# Arduino_lab_v1_2.net
KiCad netlist of a schematic drawn in EAGLE
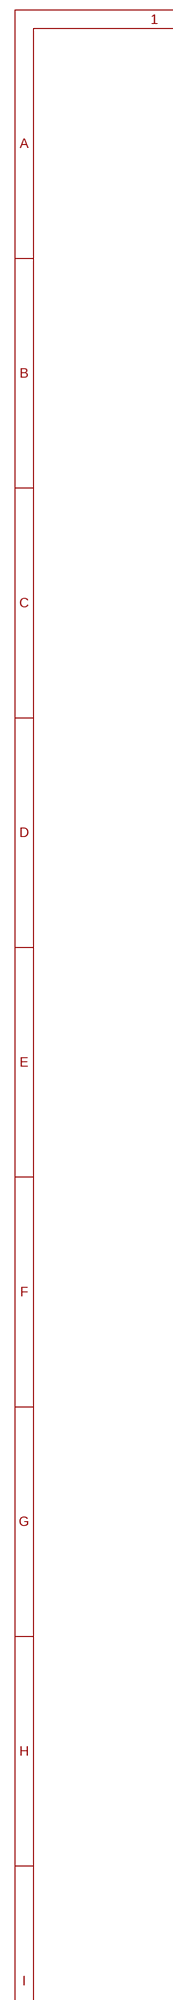
[diagram p0: schematic, sheet 1, part 1 of 2]
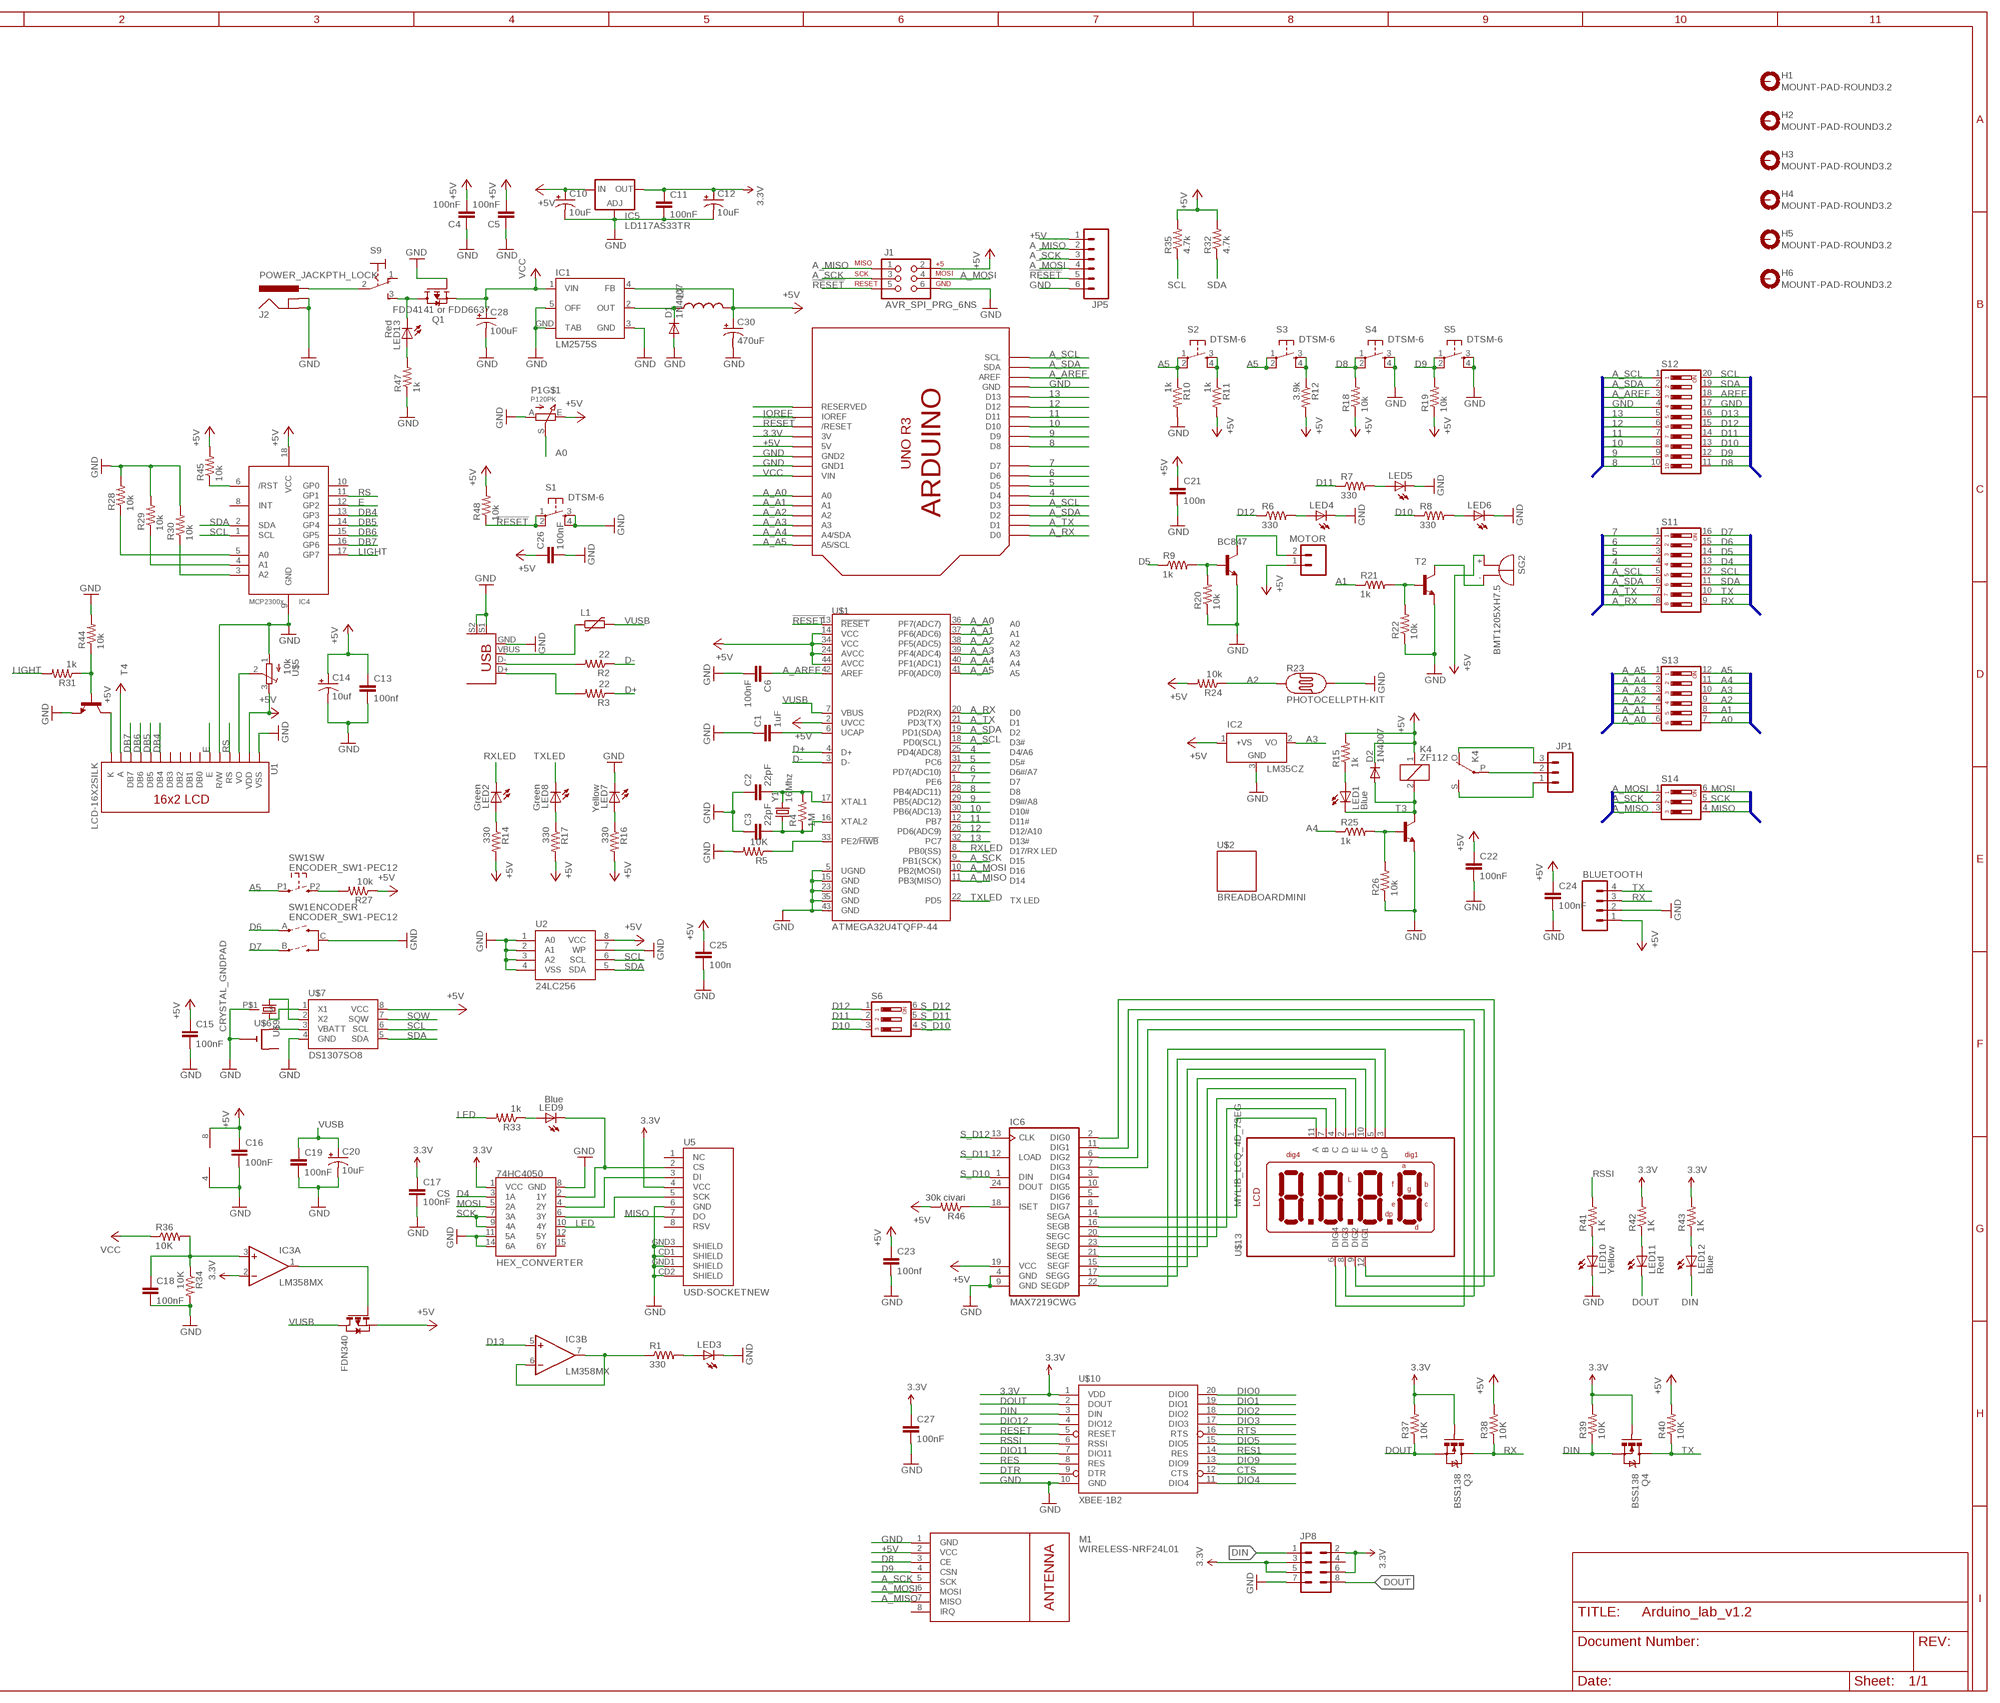
[diagram p1: schematic, sheet 1, part 2 of 2]

(export (version "E")
  (design (tool "Eeschema 10.0.6"))
  (components
    (comp (ref "74HC4050")
      (value "HEX_CONVERTER")
      (footprint "eagle-import:SO016")
      (libsource (lib "eagle-import") (part "HEX_CONVERTER"))
    )
    (comp (ref "BC847")
      (value "MMBT2222ALT1-NPN-SOT23-BEC")
      (footprint "eagle-import:SOT23-BEC")
      (libsource (lib "eagle-import") (part "-NPN-SOT23-BECMMBT2222ALT1"))
    )
    (comp (ref "BLUETOOTH")
      (value "M04PTH")
      (footprint "eagle-import:1X04")
      (libsource (lib "eagle-import") (part "M04PTH"))
    )
    (comp (ref "C1")
      (value "1uF")
      (footprint "eagle-import:1206")
      (libsource (lib "eagle-import") (part "CAP1206"))
    )
    (comp (ref "C2")
      (value "22pF")
      (footprint "eagle-import:0805")
      (libsource (lib "eagle-import") (part "CAP0805"))
    )
    (comp (ref "C3")
      (value "22pF")
      (footprint "eagle-import:0805")
      (libsource (lib "eagle-import") (part "CAP0805"))
    )
    (comp (ref "C4")
      (value "100nF")
      (footprint "eagle-import:0805")
      (libsource (lib "eagle-import") (part "CAP0805"))
    )
    (comp (ref "C5")
      (value "100nF")
      (footprint "eagle-import:0805")
      (libsource (lib "eagle-import") (part "CAP0805"))
    )
    (comp (ref "C6")
      (value "100nF")
      (footprint "eagle-import:0805")
      (libsource (lib "eagle-import") (part "CAP0805"))
    )
    (comp (ref "C10")
      (value "10uF")
      (footprint "eagle-import:EIA3216")
      (libsource (lib "eagle-import") (part "CAP_POL1206"))
    )
    (comp (ref "C11")
      (value "100nF")
      (footprint "eagle-import:0805")
      (libsource (lib "eagle-import") (part "CAP0805"))
    )
    (comp (ref "C12")
      (value "10uF")
      (footprint "eagle-import:EIA3216")
      (libsource (lib "eagle-import") (part "CAP_POL1206"))
    )
    (comp (ref "C13")
      (value "100nf")
      (footprint "eagle-import:0805")
      (libsource (lib "eagle-import") (part "CAP0805"))
    )
    (comp (ref "C14")
      (value "10uf")
      (footprint "eagle-import:EIA3216")
      (libsource (lib "eagle-import") (part "CAP_POL1206"))
    )
    (comp (ref "C15")
      (value "100nF")
      (footprint "eagle-import:0805")
      (libsource (lib "eagle-import") (part "CAP0805"))
    )
    (comp (ref "C16")
      (value "100nF")
      (footprint "eagle-import:0805")
      (libsource (lib "eagle-import") (part "CAP0805"))
    )
    (comp (ref "C17")
      (value "100nF")
      (footprint "eagle-import:0805")
      (libsource (lib "eagle-import") (part "CAP0805"))
    )
    (comp (ref "C18")
      (value "100nF")
      (footprint "eagle-import:0805")
      (libsource (lib "eagle-import") (part "CAP0805"))
    )
    (comp (ref "C19")
      (value "100nF")
      (footprint "eagle-import:0805")
      (libsource (lib "eagle-import") (part "CAP0805"))
    )
    (comp (ref "C20")
      (value "10uF")
      (footprint "eagle-import:EIA3216")
      (libsource (lib "eagle-import") (part "CAP_POL1206"))
    )
    (comp (ref "C21")
      (value "100n")
      (footprint "eagle-import:0805")
      (libsource (lib "eagle-import") (part "CAP0805"))
    )
    (comp (ref "C22")
      (value "100nF")
      (footprint "eagle-import:0805")
      (libsource (lib "eagle-import") (part "CAP0805"))
    )
    (comp (ref "C23")
      (value "100nf")
      (footprint "eagle-import:0805")
      (libsource (lib "eagle-import") (part "CAP0805"))
    )
    (comp (ref "C24")
      (value "100nF")
      (footprint "eagle-import:0805")
      (libsource (lib "eagle-import") (part "CAP0805"))
    )
    (comp (ref "C25")
      (value "100n")
      (footprint "eagle-import:0805")
      (libsource (lib "eagle-import") (part "CAP0805"))
    )
    (comp (ref "C26")
      (value "100nF")
      (footprint "eagle-import:0805")
      (libsource (lib "eagle-import") (part "CAP0805"))
    )
    (comp (ref "C27")
      (value "100nF")
      (footprint "eagle-import:0805")
      (libsource (lib "eagle-import") (part "CAP0805"))
    )
    (comp (ref "C28")
      (value "100uF")
      (footprint "eagle-import:NIPPON_F80")
      (libsource (lib "eagle-import") (part "CAP_POLF80"))
    )
    (comp (ref "C30")
      (value "470uF")
      (footprint "eagle-import:PANASONIC_G")
      (libsource (lib "eagle-import") (part "CAP_POLG"))
    )
    (comp (ref "D1")
      (value "1N4007")
      (footprint "eagle-import:SMA-DIODE_ALT")
      (libsource (lib "eagle-import") (part "DIODESMA-ALT"))
    )
    (comp (ref "D2")
      (value "1N4007")
      (footprint "eagle-import:SMA-DIODE_ALT")
      (libsource (lib "eagle-import") (part "DIODESMA-ALT"))
    )
    (comp (ref "FDN340")
      (value "PMOSSOT23")
      (footprint "eagle-import:SOT-23")
      (libsource (lib "eagle-import") (part "PMOSSOT23"))
    )
    (comp (ref "H1")
      (value "MOUNT-PAD-ROUND3.2")
      (footprint "eagle-import:3,2-PAD")
      (libsource (lib "eagle-import") (part "MOUNT-PAD-ROUND3.2"))
    )
    (comp (ref "H2")
      (value "MOUNT-PAD-ROUND3.2")
      (footprint "eagle-import:3,2-PAD")
      (libsource (lib "eagle-import") (part "MOUNT-PAD-ROUND3.2"))
    )
    (comp (ref "H3")
      (value "MOUNT-PAD-ROUND3.2")
      (footprint "eagle-import:3,2-PAD")
      (libsource (lib "eagle-import") (part "MOUNT-PAD-ROUND3.2"))
    )
    (comp (ref "H4")
      (value "MOUNT-PAD-ROUND3.2")
      (footprint "eagle-import:3,2-PAD")
      (libsource (lib "eagle-import") (part "MOUNT-PAD-ROUND3.2"))
    )
    (comp (ref "H5")
      (value "MOUNT-PAD-ROUND3.2")
      (footprint "eagle-import:3,2-PAD")
      (libsource (lib "eagle-import") (part "MOUNT-PAD-ROUND3.2"))
    )
    (comp (ref "H6")
      (value "MOUNT-PAD-ROUND3.2")
      (footprint "eagle-import:3,2-PAD")
      (libsource (lib "eagle-import") (part "MOUNT-PAD-ROUND3.2"))
    )
    (comp (ref "IC1")
      (value "LM2575S")
      (footprint "eagle-import:TO263-5")
      (libsource (lib "eagle-import") (part "LM2575S"))
    )
    (comp (ref "IC2")
      (value "LM35CZ")
      (footprint "eagle-import:TO92")
      (libsource (lib "eagle-import") (part "LM35CZ"))
    )
    (comp (ref "IC3")
      (value "LM358MX")
      (footprint "eagle-import:SO08")
      (libsource (lib "eagle-import") (part "LM358MX"))
    )
    (comp (ref "IC4")
      (value "MCP2300X/SO")
      (footprint "eagle-import:SO18W")
      (libsource (lib "eagle-import") (part "MCP2300X/SO"))
    )
    (comp (ref "IC5")
      (value "LD117AS33TR")
      (footprint "eagle-import:SOT223")
      (libsource (lib "eagle-import") (part "LD117A?S33TR"))
    )
    (comp (ref "IC6")
      (value "MAX7219CWG")
      (footprint "eagle-import:SO24W")
      (libsource (lib "eagle-import") (part "MAX7219WGC"))
    )
    (comp (ref "J1")
      (value "AVR_SPI_PRG_6NS")
      (footprint "eagle-import:2X3-NS")
      (libsource (lib "eagle-import") (part "AVR_SPI_PRG_6NS"))
    )
    (comp (ref "J2")
      (value "POWER_JACKPTH_LOCK")
      (footprint "eagle-import:POWER_JACK_PTH_LOCK")
      (libsource (lib "eagle-import") (part "POWER_JACKPTH_LOCK"))
    )
    (comp (ref "JP1")
      (value "M03-SCREW-5MM")
      (footprint "eagle-import:SCREWTERMINAL-5MM-3")
      (libsource (lib "eagle-import") (part "M03-SCREW-5MM"))
    )
    (comp (ref "JP5")
      (value "M06SIP")
      (footprint "eagle-import:1X06")
      (libsource (lib "eagle-import") (part "M06SIP"))
    )
    (comp (ref "JP8")
      (value "M04X2")
      (footprint "eagle-import:2X4")
      (libsource (lib "eagle-import") (part "M04X2"))
    )
    (comp (ref "K4")
      (value "ZF112")
      (footprint "eagle-import:ZF112")
      (libsource (lib "eagle-import") (part "ZF112"))
    )
    (comp (ref "L1")
      (value "FUSE_PTC-0805")
      (footprint "eagle-import:PTC0805")
      (libsource (lib "eagle-import") (part "FUSE_PTC-0805"))
    )
    (comp (ref "L2")
      (value "INDUCTORPWR")
      (footprint "eagle-import:CDRH125")
      (libsource (lib "eagle-import") (part "INDUCTORPWR"))
    )
    (comp (ref "LED1")
      (value "Blue")
      (footprint "eagle-import:CHIPLED_0805")
      (libsource (lib "eagle-import") (part "LEDCHIPLED_0805"))
    )
    (comp (ref "LED2")
      (value "Green")
      (footprint "eagle-import:CHIPLED_0805")
      (libsource (lib "eagle-import") (part "LEDCHIPLED_0805"))
    )
    (comp (ref "LED3")
      (value "LED5MM")
      (footprint "eagle-import:LED5MM")
      (libsource (lib "eagle-import") (part "LED5MM"))
    )
    (comp (ref "LED4")
      (value "LED5MM")
      (footprint "eagle-import:LED5MM")
      (libsource (lib "eagle-import") (part "LED5MM"))
    )
    (comp (ref "LED5")
      (value "LED5MM")
      (footprint "eagle-import:LED5MM")
      (libsource (lib "eagle-import") (part "LED5MM"))
    )
    (comp (ref "LED6")
      (value "LED5MM")
      (footprint "eagle-import:LED5MM")
      (libsource (lib "eagle-import") (part "LED5MM"))
    )
    (comp (ref "LED7")
      (value "Yellow")
      (footprint "eagle-import:CHIPLED_0805")
      (libsource (lib "eagle-import") (part "LEDCHIPLED_0805"))
    )
    (comp (ref "LED8")
      (value "Green")
      (footprint "eagle-import:CHIPLED_0805")
      (libsource (lib "eagle-import") (part "LEDCHIPLED_0805"))
    )
    (comp (ref "LED9")
      (value "Blue")
      (footprint "eagle-import:CHIPLED_0805")
      (libsource (lib "eagle-import") (part "LEDCHIPLED_0805"))
    )
    (comp (ref "LED10")
      (value "Yellow")
      (footprint "eagle-import:CHIPLED_0805")
      (libsource (lib "eagle-import") (part "LEDCHIPLED_0805"))
    )
    (comp (ref "LED11")
      (value "Red")
      (footprint "eagle-import:CHIPLED_0805")
      (libsource (lib "eagle-import") (part "LEDCHIPLED_0805"))
    )
    (comp (ref "LED12")
      (value "Blue")
      (footprint "eagle-import:CHIPLED_0805")
      (libsource (lib "eagle-import") (part "LEDCHIPLED_0805"))
    )
    (comp (ref "LED13")
      (value "Red")
      (footprint "eagle-import:CHIPLED_0805")
      (libsource (lib "eagle-import") (part "LEDCHIPLED_0805"))
    )
    (comp (ref "M1")
      (value "WIRELESS-NRF24L01")
      (footprint "eagle-import:WIRELESS-NRF24L01")
      (libsource (lib "eagle-import") (part "WIRELESS-NRF24L01"))
    )
    (comp (ref "MOTOR")
      (value "M023.5MM")
      (footprint "eagle-import:SCREWTERMINAL-3.5MM-2")
      (libsource (lib "eagle-import") (part "M023.5MM"))
    )
    (comp (ref "P1")
      (value "P120PK")
      (footprint "eagle-import:P120PK")
      (libsource (lib "eagle-import") (part "P120PK"))
    )
    (comp (ref "Q1")
      (value "FDD4141 or FDD6637")
      (footprint "eagle-import:TO252")
      (libsource (lib "eagle-import") (part "FDD4141TO252"))
    )
    (comp (ref "Q3")
      (value "BSS138")
      (footprint "eagle-import:SOT23-3")
      (libsource (lib "eagle-import") (part "MOSFET-NCHANNELSMD"))
    )
    (comp (ref "Q4")
      (value "BSS138")
      (footprint "eagle-import:SOT23-3")
      (libsource (lib "eagle-import") (part "MOSFET-NCHANNELSMD"))
    )
    (comp (ref "R1")
      (value "330")
      (footprint "eagle-import:0805")
      (libsource (lib "eagle-import") (part "RESISTOR0805-RES"))
    )
    (comp (ref "R2")
      (value "22")
      (footprint "eagle-import:0805")
      (libsource (lib "eagle-import") (part "RESISTOR0805-RES"))
    )
    (comp (ref "R3")
      (value "22")
      (footprint "eagle-import:0805")
      (libsource (lib "eagle-import") (part "RESISTOR0805-RES"))
    )
    (comp (ref "R4")
      (value "1M")
      (footprint "eagle-import:0805")
      (libsource (lib "eagle-import") (part "RESISTOR0805-RES"))
    )
    (comp (ref "R5")
      (value "10K")
      (footprint "eagle-import:0805")
      (libsource (lib "eagle-import") (part "RESISTOR0805-RES"))
    )
    (comp (ref "R6")
      (value "330")
      (footprint "eagle-import:0805")
      (libsource (lib "eagle-import") (part "RESISTOR0805-RES"))
    )
    (comp (ref "R7")
      (value "330")
      (footprint "eagle-import:0805")
      (libsource (lib "eagle-import") (part "RESISTOR0805-RES"))
    )
    (comp (ref "R8")
      (value "330")
      (footprint "eagle-import:0805")
      (libsource (lib "eagle-import") (part "RESISTOR0805-RES"))
    )
    (comp (ref "R9")
      (value "1k")
      (footprint "eagle-import:0805")
      (libsource (lib "eagle-import") (part "RESISTOR0805-RES"))
    )
    (comp (ref "R10")
      (value "1k")
      (footprint "eagle-import:0805")
      (libsource (lib "eagle-import") (part "RESISTOR0805-RES"))
    )
    (comp (ref "R11")
      (value "1k")
      (footprint "eagle-import:0805")
      (libsource (lib "eagle-import") (part "RESISTOR0805-RES"))
    )
    (comp (ref "R12")
      (value "3.9k")
      (footprint "eagle-import:0805")
      (libsource (lib "eagle-import") (part "RESISTOR0805-RES"))
    )
    (comp (ref "R14")
      (value "330")
      (footprint "eagle-import:0805")
      (libsource (lib "eagle-import") (part "RESISTOR0805-RES"))
    )
    (comp (ref "R15")
      (value "1k")
      (footprint "eagle-import:0805")
      (libsource (lib "eagle-import") (part "RESISTOR0805-RES"))
    )
    (comp (ref "R16")
      (value "330")
      (footprint "eagle-import:0805")
      (libsource (lib "eagle-import") (part "RESISTOR0805-RES"))
    )
    (comp (ref "R17")
      (value "330")
      (footprint "eagle-import:0805")
      (libsource (lib "eagle-import") (part "RESISTOR0805-RES"))
    )
    (comp (ref "R18")
      (value "10k")
      (footprint "eagle-import:0805")
      (libsource (lib "eagle-import") (part "RESISTOR0805-RES"))
    )
    (comp (ref "R19")
      (value "10k")
      (footprint "eagle-import:0805")
      (libsource (lib "eagle-import") (part "RESISTOR0805-RES"))
    )
    (comp (ref "R20")
      (value "10k")
      (footprint "eagle-import:0805")
      (libsource (lib "eagle-import") (part "RESISTOR0805-RES"))
    )
    (comp (ref "R21")
      (value "1k")
      (footprint "eagle-import:0805")
      (libsource (lib "eagle-import") (part "RESISTOR0805-RES"))
    )
    (comp (ref "R22")
      (value "10k")
      (footprint "eagle-import:0805")
      (libsource (lib "eagle-import") (part "RESISTOR0805-RES"))
    )
    (comp (ref "R23")
      (value "PHOTOCELLPTH-KIT")
      (footprint "eagle-import:PHOTOCELL-KIT")
      (libsource (lib "eagle-import") (part "PHOTOCELLPTH-KIT"))
    )
    (comp (ref "R24")
      (value "10k")
      (footprint "eagle-import:0805")
      (libsource (lib "eagle-import") (part "RESISTOR0805-RES"))
    )
    (comp (ref "R25")
      (value "1k")
      (footprint "eagle-import:0805")
      (libsource (lib "eagle-import") (part "RESISTOR0805-RES"))
    )
    (comp (ref "R26")
      (value "10k")
      (footprint "eagle-import:0805")
      (libsource (lib "eagle-import") (part "RESISTOR0805-RES"))
    )
    (comp (ref "R27")
      (value "10k")
      (footprint "eagle-import:0805")
      (libsource (lib "eagle-import") (part "RESISTOR0805-RES"))
    )
    (comp (ref "R28")
      (value "10k")
      (footprint "eagle-import:0805")
      (libsource (lib "eagle-import") (part "RESISTOR0805-RES"))
    )
    (comp (ref "R29")
      (value "10k")
      (footprint "eagle-import:0805")
      (libsource (lib "eagle-import") (part "RESISTOR0805-RES"))
    )
    (comp (ref "R30")
      (value "10k")
      (footprint "eagle-import:0805")
      (libsource (lib "eagle-import") (part "RESISTOR0805-RES"))
    )
    (comp (ref "R31")
      (value "1k")
      (footprint "eagle-import:0805")
      (libsource (lib "eagle-import") (part "RESISTOR0805-RES"))
    )
    (comp (ref "R32")
      (value "4.7k")
      (footprint "eagle-import:0805")
      (libsource (lib "eagle-import") (part "RESISTOR0805-RES"))
    )
    (comp (ref "R33")
      (value "1k")
      (footprint "eagle-import:0805")
      (libsource (lib "eagle-import") (part "RESISTOR0805-RES"))
    )
    (comp (ref "R34")
      (value "10K")
      (footprint "eagle-import:0805")
      (libsource (lib "eagle-import") (part "RESISTOR0805-RES"))
    )
    (comp (ref "R35")
      (value "4.7k")
      (footprint "eagle-import:0805")
      (libsource (lib "eagle-import") (part "RESISTOR0805-RES"))
    )
    (comp (ref "R36")
      (value "10K")
      (footprint "eagle-import:0805")
      (libsource (lib "eagle-import") (part "RESISTOR0805-RES"))
    )
    (comp (ref "R37")
      (value "10K")
      (footprint "eagle-import:0805")
      (libsource (lib "eagle-import") (part "RESISTOR0805-RES"))
    )
    (comp (ref "R38")
      (value "10K")
      (footprint "eagle-import:0805")
      (libsource (lib "eagle-import") (part "RESISTOR0805-RES"))
    )
    (comp (ref "R39")
      (value "10K")
      (footprint "eagle-import:0805")
      (libsource (lib "eagle-import") (part "RESISTOR0805-RES"))
    )
    (comp (ref "R40")
      (value "10K")
      (footprint "eagle-import:0805")
      (libsource (lib "eagle-import") (part "RESISTOR0805-RES"))
    )
    (comp (ref "R41")
      (value "1K")
      (footprint "eagle-import:0805")
      (libsource (lib "eagle-import") (part "RESISTOR0805-RES"))
    )
    (comp (ref "R42")
      (value "1K")
      (footprint "eagle-import:0805")
      (libsource (lib "eagle-import") (part "RESISTOR0805-RES"))
    )
    (comp (ref "R43")
      (value "1K")
      (footprint "eagle-import:0805")
      (libsource (lib "eagle-import") (part "RESISTOR0805-RES"))
    )
    (comp (ref "R44")
      (value "10k")
      (footprint "eagle-import:0805")
      (libsource (lib "eagle-import") (part "RESISTOR0805-RES"))
    )
    (comp (ref "R45")
      (value "10k")
      (footprint "eagle-import:0805")
      (libsource (lib "eagle-import") (part "RESISTOR0805-RES"))
    )
    (comp (ref "R46")
      (value "30k civari")
      (footprint "eagle-import:0805")
      (libsource (lib "eagle-import") (part "RESISTOR0805-RES"))
    )
    (comp (ref "R47")
      (value "1k")
      (footprint "eagle-import:0805")
      (libsource (lib "eagle-import") (part "RESISTOR0805-RES"))
    )
    (comp (ref "R48")
      (value "10k")
      (footprint "eagle-import:0805")
      (libsource (lib "eagle-import") (part "RESISTOR0805-RES"))
    )
    (comp (ref "S1")
      (value "DTSM-6")
      (footprint "eagle-import:DTSM-6")
      (libsource (lib "eagle-import") (part "DTSM-6"))
    )
    (comp (ref "S2")
      (value "DTSM-6")
      (footprint "eagle-import:DTSM-6")
      (libsource (lib "eagle-import") (part "DTSM-6"))
    )
    (comp (ref "S3")
      (value "DTSM-6")
      (footprint "eagle-import:DTSM-6")
      (libsource (lib "eagle-import") (part "DTSM-6"))
    )
    (comp (ref "S4")
      (value "DTSM-6")
      (footprint "eagle-import:DTSM-6")
      (libsource (lib "eagle-import") (part "DTSM-6"))
    )
    (comp (ref "S5")
      (value "DTSM-6")
      (footprint "eagle-import:DTSM-6")
      (libsource (lib "eagle-import") (part "DTSM-6"))
    )
    (comp (ref "S6")
      (value "DIP03YL")
      (footprint "eagle-import:DIP03YL")
      (fields (field (name "OC_FARNELL") "unknown") (field (name "OC_NEWARK") "unknown"))
      (libsource (lib "eagle-import") (part "DIP03YL"))
    )
    (comp (ref "S9")
      (value "M9040P")
      (footprint "eagle-import:M9040P")
      (libsource (lib "eagle-import") (part "M9040P"))
    )
    (comp (ref "S11")
      (value "DIP08YL")
      (footprint "eagle-import:DIP08YL")
      (libsource (lib "eagle-import") (part "DIP08YL"))
    )
    (comp (ref "S12")
      (value "DIP10YL")
      (footprint "eagle-import:DIP10YL")
      (libsource (lib "eagle-import") (part "DIP10YL"))
    )
    (comp (ref "S13")
      (value "DIP06YL")
      (footprint "eagle-import:DIP06YL")
      (libsource (lib "eagle-import") (part "DIP06YL"))
    )
    (comp (ref "S14")
      (value "DIP03YL")
      (footprint "eagle-import:DIP03YL")
      (libsource (lib "eagle-import") (part "DIP03YL"))
    )
    (comp (ref "SG2")
      (value "BMT1205XH7.5")
      (footprint "eagle-import:BMT1205XH7.5")
      (libsource (lib "eagle-import") (part "BMT1205XH7.5"))
    )
    (comp (ref "SW1")
      (value "ENCODER_SW1-PEC12")
      (footprint "eagle-import:PEC12_INCREMENTAL_ENCODER")
      (libsource (lib "eagle-import") (part "ENCODER_SW1-PEC12"))
    )
    (comp (ref "T2")
      (value "MMBT2222ALT1-NPN-SOT23-BEC")
      (footprint "eagle-import:SOT23-BEC")
      (libsource (lib "eagle-import") (part "-NPN-SOT23-BECMMBT2222ALT1"))
    )
    (comp (ref "T3")
      (value "MMBT2222ALT1-NPN-SOT23-BEC")
      (footprint "eagle-import:SOT23-BEC")
      (libsource (lib "eagle-import") (part "-NPN-SOT23-BECMMBT2222ALT1"))
    )
    (comp (ref "T4")
      (value "MMBT2222ALT1-NPN-SOT23-BEC")
      (footprint "eagle-import:SOT23-BEC")
      (libsource (lib "eagle-import") (part "-NPN-SOT23-BECMMBT2222ALT1"))
    )
    (comp (ref "U$1")
      (value "ATMEGA32U4TQFP-44")
      (footprint "eagle-import:TQFP44")
      (libsource (lib "eagle-import") (part "ATMEGA32U4TQFP-44"))
    )
    (comp (ref "U$2")
      (value "BREADBOARDMINI")
      (footprint "eagle-import:BREADBOARD-MINI")
      (libsource (lib "eagle-import") (part "BREADBOARDMINI"))
    )
    (comp (ref "U$3")
      (value "USB+SHIELD")
      (footprint "eagle-import:USB-B-PTH")
      (libsource (lib "eagle-import") (part "USB+SHIELD"))
    )
    (comp (ref "U$4")
      (value "UNO_R3")
      (footprint "eagle-import:UNO_R3")
      (libsource (lib "eagle-import") (part "UNO_R3"))
    )
    (comp (ref "U$5")
      (value "10k")
      (footprint "eagle-import:TC33X")
      (libsource (lib "eagle-import") (part "TRIMPOTTC33X"))
    )
    (comp (ref "U$6")
      (value "CR1220SMT")
      (footprint "eagle-import:CR1220-SMD")
      (libsource (lib "eagle-import") (part "CR1220SMT"))
    )
    (comp (ref "U$7")
      (value "DS1307SO8")
      (footprint "eagle-import:SO08")
      (libsource (lib "eagle-import") (part "DS1307SO8"))
    )
    (comp (ref "U$9")
      (value "CRYSTAL_GNDPAD")
      (footprint "eagle-import:TC38H_GNDPAD")
      (libsource (lib "eagle-import") (part "CRYSTAL_GNDPAD"))
    )
    (comp (ref "U$10")
      (value "XBEE-1B2")
      (footprint "eagle-import:XBEE-SILK")
      (libsource (lib "eagle-import") (part "XBEE-1B2"))
    )
    (comp (ref "U$13")
      (value "MYLIB_LCQ_4D_7SEG")
      (footprint "eagle-import:MYLIB_LDQ_4D_7SEG")
      (libsource (lib "eagle-import") (part "MYLIB_LCQ_4D_7SEG"))
    )
    (comp (ref "U1")
      (value "LCD-16X2SILK")
      (footprint "eagle-import:LCD-16X2")
      (libsource (lib "eagle-import") (part "LCD-16X2SILK"))
    )
    (comp (ref "U2")
      (value "24LC256")
      (footprint "eagle-import:SO08")
      (libsource (lib "eagle-import") (part "EEPROM-I2CSMD"))
    )
    (comp (ref "U5")
      (value "USD-SOCKETNEW")
      (footprint "eagle-import:MICRO-SD-SOCKET-PP")
      (libsource (lib "eagle-import") (part "USD-SOCKETNEW"))
    )
    (comp (ref "Y1")
      (value "16Mhz")
      (footprint "eagle-import:CRYSTAL-SMD-5X3")
      (libsource (lib "eagle-import") (part "CRYSTAL5X3"))
    )
  )
  (nets
    (net (code "1") (name "+5V") (class "Default")
      (node (ref "BLUETOOTH") (pin "1") (pinfunction "1_1") (pintype "passive"))
      (node (ref "C10") (pin "A") (pinfunction "+_A") (pintype "passive"))
      (node (ref "C13") (pin "1") (pinfunction "1_1") (pintype "passive"))
      (node (ref "C14") (pin "A") (pinfunction "+_A") (pintype "passive"))
      (node (ref "C15") (pin "1") (pinfunction "1_1") (pintype "passive"))
      (node (ref "C16") (pin "1") (pinfunction "1_1") (pintype "passive"))
      (node (ref "C21") (pin "1") (pinfunction "1_1") (pintype "passive"))
      (node (ref "C22") (pin "1") (pinfunction "1_1") (pintype "passive"))
      (node (ref "C23") (pin "1") (pinfunction "1_1") (pintype "passive"))
      (node (ref "C24") (pin "1") (pinfunction "1_1") (pintype "passive"))
      (node (ref "C25") (pin "1") (pinfunction "1_1") (pintype "passive"))
      (node (ref "C26") (pin "1") (pinfunction "1_1") (pintype "passive"))
      (node (ref "C30") (pin "+") (pinfunction "+_+") (pintype "passive"))
      (node (ref "C4") (pin "2") (pinfunction "2_2") (pintype "passive"))
      (node (ref "C5") (pin "2") (pinfunction "2_2") (pintype "passive"))
      (node (ref "D2") (pin "C") (pinfunction "C_C") (pintype "passive"))
      (node (ref "FDN340") (pin "2") (pinfunction "S_2") (pintype "passive"))
      (node (ref "IC1") (pin "4") (pinfunction "FB_4") (pintype "input"))
      (node (ref "IC2") (pin "1") (pinfunction "+VS_1") (pintype "input"))
      (node (ref "IC3") (pin "8") (pinfunction "V+_8") (pintype "power_in"))
      (node (ref "IC4") (pin "18") (pinfunction "VCC_18") (pintype "power_in"))
      (node (ref "IC5") (pin "3") (pinfunction "IN_3") (pintype "input"))
      (node (ref "IC6") (pin "19") (pinfunction "VCC_19") (pintype "power_in"))
      (node (ref "J1") (pin "2") (pinfunction "2_2") (pintype "passive"))
      (node (ref "JP5") (pin "1") (pinfunction "1_1") (pintype "passive"))
      (node (ref "K4") (pin "1") (pinfunction "1_1") (pintype "passive"))
      (node (ref "L2") (pin "2") (pinfunction "2_2") (pintype "passive"))
      (node (ref "M1") (pin "2") (pinfunction "VCC_2") (pintype "power_in"))
      (node (ref "MOTOR") (pin "1") (pinfunction "1_1") (pintype "passive"))
      (node (ref "P1") (pin "E") (pinfunction "E_E") (pintype "passive"))
      (node (ref "R11") (pin "2") (pinfunction "2_2") (pintype "passive"))
      (node (ref "R12") (pin "2") (pinfunction "2_2") (pintype "passive"))
      (node (ref "R14") (pin "2") (pinfunction "2_2") (pintype "passive"))
      (node (ref "R15") (pin "2") (pinfunction "2_2") (pintype "passive"))
      (node (ref "R16") (pin "2") (pinfunction "2_2") (pintype "passive"))
      (node (ref "R17") (pin "2") (pinfunction "2_2") (pintype "passive"))
      (node (ref "R18") (pin "1") (pinfunction "1_1") (pintype "passive"))
      (node (ref "R19") (pin "1") (pinfunction "1_1") (pintype "passive"))
      (node (ref "R24") (pin "2") (pinfunction "2_2") (pintype "passive"))
      (node (ref "R27") (pin "1") (pinfunction "1_1") (pintype "passive"))
      (node (ref "R32") (pin "2") (pinfunction "2_2") (pintype "passive"))
      (node (ref "R35") (pin "2") (pinfunction "2_2") (pintype "passive"))
      (node (ref "R38") (pin "2") (pinfunction "2_2") (pintype "passive"))
      (node (ref "R40") (pin "2") (pinfunction "2_2") (pintype "passive"))
      (node (ref "R45") (pin "2") (pinfunction "2_2") (pintype "passive"))
      (node (ref "R46") (pin "2") (pinfunction "2_2") (pintype "passive"))
      (node (ref "R48") (pin "2") (pinfunction "2_2") (pintype "passive"))
      (node (ref "SG2") (pin "+") (pinfunction "+_+") (pintype "passive"))
      (node (ref "U$1") (pin "14") (pinfunction "VCC_14") (pintype "bidirectional"))
      (node (ref "U$1") (pin "2") (pinfunction "UVCC_2") (pintype "bidirectional"))
      (node (ref "U$1") (pin "24") (pinfunction "AVCC_24") (pintype "bidirectional"))
      (node (ref "U$1") (pin "34") (pinfunction "VCC_34") (pintype "bidirectional"))
      (node (ref "U$1") (pin "44") (pinfunction "AVCC_44") (pintype "bidirectional"))
      (node (ref "U$4") (pin "5V") (pinfunction "5V_5V") (pintype "power_in"))
      (node (ref "U$5") (pin "3") (pinfunction "E_3") (pintype "passive"))
      (node (ref "U$7") (pin "8") (pinfunction "VCC_8") (pintype "bidirectional"))
      (node (ref "U1") (pin "15") (pinfunction "A_15") (pintype "power_in"))
      (node (ref "U1") (pin "2") (pinfunction "VDD_2") (pintype "power_in"))
      (node (ref "U2") (pin "8") (pinfunction "VCC_8") (pintype "power_in"))
    )
    (net (code "2") (name "/4") (class "Default")
      (node (ref "S11") (pin "4") (pinfunction "4_4") (pintype "passive"))
      (node (ref "U$1") (pin "25") (pinfunction "PD4(ADC8)_25") (pintype "bidirectional"))
      (node (ref "U$4") (pin "D4") (pinfunction "D4_D4") (pintype "bidirectional"))
    )
    (net (code "3") (name "/5") (class "Default")
      (node (ref "S11") (pin "3") (pinfunction "3_3") (pintype "passive"))
      (node (ref "U$1") (pin "31") (pinfunction "PC6_31") (pintype "bidirectional"))
      (node (ref "U$4") (pin "D5") (pinfunction "D5_D5") (pintype "bidirectional"))
    )
    (net (code "4") (name "/6") (class "Default")
      (node (ref "S11") (pin "2") (pinfunction "2_2") (pintype "passive"))
      (node (ref "U$1") (pin "27") (pinfunction "PD7(ADC10)_27") (pintype "bidirectional"))
      (node (ref "U$4") (pin "D6") (pinfunction "D6_D6") (pintype "bidirectional"))
    )
    (net (code "5") (name "/7") (class "Default")
      (node (ref "S11") (pin "1") (pinfunction "1_1") (pintype "passive"))
      (node (ref "U$1") (pin "1") (pinfunction "PE6_1") (pintype "bidirectional"))
      (node (ref "U$4") (pin "D7") (pinfunction "D7_D7") (pintype "bidirectional"))
    )
    (net (code "6") (name "/8") (class "Default")
      (node (ref "S12") (pin "10") (pinfunction "10_10") (pintype "passive"))
      (node (ref "U$1") (pin "28") (pinfunction "PB4(ADC11)_28") (pintype "bidirectional"))
      (node (ref "U$4") (pin "D8") (pinfunction "D8_D8") (pintype "bidirectional"))
    )
    (net (code "7") (name "/9") (class "Default")
      (node (ref "S12") (pin "9") (pinfunction "9_9") (pintype "passive"))
      (node (ref "U$1") (pin "29") (pinfunction "PB5(ADC12)_29") (pintype "bidirectional"))
      (node (ref "U$4") (pin "D9") (pinfunction "D9_D9") (pintype "bidirectional"))
    )
    (net (code "8") (name "/10") (class "Default")
      (node (ref "S12") (pin "8") (pinfunction "8_8") (pintype "passive"))
      (node (ref "U$1") (pin "30") (pinfunction "PB6(ADC13)_30") (pintype "bidirectional"))
      (node (ref "U$4") (pin "D10") (pinfunction "D10_D10") (pintype "bidirectional"))
    )
    (net (code "9") (name "/11") (class "Default")
      (node (ref "S12") (pin "7") (pinfunction "7_7") (pintype "passive"))
      (node (ref "U$1") (pin "12") (pinfunction "PB7_12") (pintype "bidirectional"))
      (node (ref "U$4") (pin "D11") (pinfunction "D11_D11") (pintype "bidirectional"))
    )
    (net (code "10") (name "/12") (class "Default")
      (node (ref "S12") (pin "6") (pinfunction "6_6") (pintype "passive"))
      (node (ref "U$1") (pin "26") (pinfunction "PD6(ADC9)_26") (pintype "bidirectional"))
      (node (ref "U$4") (pin "D12") (pinfunction "D12_D12") (pintype "bidirectional"))
    )
    (net (code "11") (name "/13") (class "Default")
      (node (ref "S12") (pin "5") (pinfunction "5_5") (pintype "passive"))
      (node (ref "U$1") (pin "32") (pinfunction "PC7_32") (pintype "bidirectional"))
      (node (ref "U$4") (pin "D13") (pinfunction "D13_D13") (pintype "bidirectional"))
    )
    (net (code "12") (name "/A0") (class "Default")
      (node (ref "P1") (pin "S") (pinfunction "S_S") (pintype "passive"))
      (node (ref "S13") (pin "7") (pinfunction "7_7") (pintype "passive"))
    )
    (net (code "13") (name "/A1") (class "Default")
      (node (ref "R21") (pin "1") (pinfunction "1_1") (pintype "passive"))
      (node (ref "S13") (pin "8") (pinfunction "8_8") (pintype "passive"))
    )
    (net (code "14") (name "/A2") (class "Default")
      (node (ref "R23") (pin "1") (pinfunction "P$1_1") (pintype "bidirectional"))
      (node (ref "R24") (pin "1") (pinfunction "1_1") (pintype "passive"))
      (node (ref "S13") (pin "9") (pinfunction "9_9") (pintype "passive"))
    )
    (net (code "15") (name "/A3") (class "Default")
      (node (ref "IC2") (pin "2") (pinfunction "VO_2") (pintype "input"))
      (node (ref "S13") (pin "10") (pinfunction "10_10") (pintype "passive"))
    )
    (net (code "16") (name "/A4") (class "Default")
      (node (ref "R25") (pin "1") (pinfunction "1_1") (pintype "passive"))
      (node (ref "S13") (pin "11") (pinfunction "11_11") (pintype "passive"))
    )
    (net (code "17") (name "/A5") (class "Default")
      (node (ref "R10") (pin "1") (pinfunction "1_1") (pintype "passive"))
      (node (ref "S13") (pin "12") (pinfunction "12_12") (pintype "passive"))
      (node (ref "S2") (pin "1") (pinfunction "1_1") (pintype "passive"))
      (node (ref "S2") (pin "2") (pinfunction "2_2") (pintype "passive"))
      (node (ref "S3") (pin "1") (pinfunction "1_1") (pintype "passive"))
      (node (ref "S3") (pin "2") (pinfunction "2_2") (pintype "passive"))
      (node (ref "SW1") (pin "P1") (pinfunction "1_P1") (pintype "passive"))
    )
    (net (code "18") (name "/AREF") (class "Default")
      (node (ref "S12") (pin "18") (pinfunction "18_18") (pintype "passive"))
    )
    (net (code "19") (name "/A_A0") (class "Default")
      (node (ref "S13") (pin "6") (pinfunction "6_6") (pintype "passive"))
      (node (ref "U$1") (pin "36") (pinfunction "PF7(ADC7)_36") (pintype "bidirectional"))
      (node (ref "U$4") (pin "A0") (pinfunction "A0_A0") (pintype "bidirectional"))
    )
    (net (code "20") (name "/A_A1") (class "Default")
      (node (ref "S13") (pin "5") (pinfunction "5_5") (pintype "passive"))
      (node (ref "U$1") (pin "37") (pinfunction "PF6(ADC6)_37") (pintype "bidirectional"))
      (node (ref "U$4") (pin "A1") (pinfunction "A1_A1") (pintype "bidirectional"))
    )
    (net (code "21") (name "/A_A2") (class "Default")
      (node (ref "S13") (pin "4") (pinfunction "4_4") (pintype "passive"))
      (node (ref "U$1") (pin "38") (pinfunction "PF5(ADC5)_38") (pintype "bidirectional"))
      (node (ref "U$4") (pin "A2") (pinfunction "A2_A2") (pintype "bidirectional"))
    )
    (net (code "22") (name "/A_A3") (class "Default")
      (node (ref "S13") (pin "3") (pinfunction "3_3") (pintype "passive"))
      (node (ref "U$1") (pin "39") (pinfunction "PF4(ADC4)_39") (pintype "bidirectional"))
      (node (ref "U$4") (pin "A3") (pinfunction "A3_A3") (pintype "bidirectional"))
    )
    (net (code "23") (name "/A_A4") (class "Default")
      (node (ref "S13") (pin "2") (pinfunction "2_2") (pintype "passive"))
      (node (ref "U$1") (pin "40") (pinfunction "PF1(ADC1)_40") (pintype "bidirectional"))
      (node (ref "U$4") (pin "A4") (pinfunction "A4/SDA_A4") (pintype "bidirectional"))
    )
    (net (code "24") (name "/A_A5") (class "Default")
      (node (ref "S13") (pin "1") (pinfunction "1_1") (pintype "passive"))
      (node (ref "U$1") (pin "41") (pinfunction "PF0(ADC0)_41") (pintype "bidirectional"))
      (node (ref "U$4") (pin "A5") (pinfunction "A5/SCL_A5") (pintype "bidirectional"))
    )
    (net (code "25") (name "/A_AREF") (class "Default")
      (node (ref "C6") (pin "1") (pinfunction "1_1") (pintype "passive"))
      (node (ref "S12") (pin "3") (pinfunction "3_3") (pintype "passive"))
      (node (ref "U$1") (pin "42") (pinfunction "AREF_42") (pintype "bidirectional"))
      (node (ref "U$4") (pin "AREF") (pinfunction "AREF_AREF") (pintype "bidirectional"))
    )
    (net (code "26") (name "/A_MISO") (class "Default")
      (node (ref "J1") (pin "1") (pinfunction "1_1") (pintype "passive"))
      (node (ref "JP5") (pin "2") (pinfunction "2_2") (pintype "passive"))
      (node (ref "M1") (pin "7") (pinfunction "MISO_7") (pintype "bidirectional"))
      (node (ref "S14") (pin "3") (pinfunction "3_3") (pintype "passive"))
      (node (ref "U$1") (pin "11") (pinfunction "PB3(MISO)_11") (pintype "bidirectional"))
    )
    (net (code "27") (name "/A_MOSI") (class "Default")
      (node (ref "J1") (pin "4") (pinfunction "4_4") (pintype "passive"))
      (node (ref "JP5") (pin "4") (pinfunction "4_4") (pintype "passive"))
      (node (ref "M1") (pin "6") (pinfunction "MOSI_6") (pintype "bidirectional"))
      (node (ref "S14") (pin "1") (pinfunction "1_1") (pintype "passive"))
      (node (ref "U$1") (pin "10") (pinfunction "PB2(MOSI)_10") (pintype "bidirectional"))
    )
    (net (code "28") (name "/A_RX") (class "Default")
      (node (ref "S11") (pin "8") (pinfunction "8_8") (pintype "passive"))
      (node (ref "U$1") (pin "20") (pinfunction "PD2(RX)_20") (pintype "bidirectional"))
      (node (ref "U$4") (pin "D0") (pinfunction "D0_D0") (pintype "bidirectional"))
    )
    (net (code "29") (name "/A_SCK") (class "Default")
      (node (ref "J1") (pin "3") (pinfunction "3_3") (pintype "passive"))
      (node (ref "JP5") (pin "3") (pinfunction "3_3") (pintype "passive"))
      (node (ref "M1") (pin "5") (pinfunction "SCK_5") (pintype "bidirectional"))
      (node (ref "S14") (pin "2") (pinfunction "2_2") (pintype "passive"))
      (node (ref "U$1") (pin "9") (pinfunction "PB1(SCK)_9") (pintype "bidirectional"))
    )
    (net (code "30") (name "/A_SCL") (class "Default")
      (node (ref "S11") (pin "5") (pinfunction "5_5") (pintype "passive"))
      (node (ref "S12") (pin "1") (pinfunction "1_1") (pintype "passive"))
      (node (ref "U$1") (pin "18") (pinfunction "PD0(SCL)_18") (pintype "bidirectional"))
      (node (ref "U$4") (pin "D3") (pinfunction "D3_D3") (pintype "bidirectional"))
      (node (ref "U$4") (pin "SCL") (pinfunction "SCL_SCL") (pintype "bidirectional"))
    )
    (net (code "31") (name "/A_SDA") (class "Default")
      (node (ref "S11") (pin "6") (pinfunction "6_6") (pintype "passive"))
      (node (ref "S12") (pin "2") (pinfunction "2_2") (pintype "passive"))
      (node (ref "U$1") (pin "19") (pinfunction "PD1(SDA)_19") (pintype "bidirectional"))
      (node (ref "U$4") (pin "D2") (pinfunction "D2_D2") (pintype "bidirectional"))
      (node (ref "U$4") (pin "SDA") (pinfunction "SDA_SDA") (pintype "bidirectional"))
    )
    (net (code "32") (name "/A_TX") (class "Default")
      (node (ref "S11") (pin "7") (pinfunction "7_7") (pintype "passive"))
      (node (ref "U$1") (pin "21") (pinfunction "PD3(TX)_21") (pintype "bidirectional"))
      (node (ref "U$4") (pin "D1") (pinfunction "D1_D1") (pintype "bidirectional"))
    )
    (net (code "33") (name "/CTS") (class "Default")
      (node (ref "U$10") (pin "12") (pinfunction "CTS_12") (pintype "output"))
    )
    (net (code "34") (name "/D+") (class "Default")
      (node (ref "R3") (pin "1") (pinfunction "1_1") (pintype "passive"))
      (node (ref "U$1") (pin "4") (pinfunction "D+_4") (pintype "bidirectional"))
    )
    (net (code "35") (name "/D-") (class "Default")
      (node (ref "R2") (pin "1") (pinfunction "1_1") (pintype "passive"))
      (node (ref "U$1") (pin "3") (pinfunction "D-_3") (pintype "bidirectional"))
    )
    (net (code "36") (name "/D4") (class "Default")
      (node (ref "74HC4050") (pin "3") (pinfunction "1A_3") (pintype "bidirectional"))
      (node (ref "S11") (pin "13") (pinfunction "13_13") (pintype "passive"))
    )
    (net (code "37") (name "/D5") (class "Default")
      (node (ref "R9") (pin "1") (pinfunction "1_1") (pintype "passive"))
      (node (ref "S11") (pin "14") (pinfunction "14_14") (pintype "passive"))
    )
    (net (code "38") (name "/D6") (class "Default")
      (node (ref "S11") (pin "15") (pinfunction "15_15") (pintype "passive"))
      (node (ref "SW1") (pin "A") (pinfunction "A_A") (pintype "passive"))
    )
    (net (code "39") (name "/D7") (class "Default")
      (node (ref "S11") (pin "16") (pinfunction "16_16") (pintype "passive"))
      (node (ref "SW1") (pin "B") (pinfunction "B_B") (pintype "passive"))
    )
    (net (code "40") (name "/D8") (class "Default")
      (node (ref "M1") (pin "3") (pinfunction "CE_3") (pintype "bidirectional"))
      (node (ref "R18") (pin "2") (pinfunction "2_2") (pintype "passive"))
      (node (ref "S12") (pin "11") (pinfunction "11_11") (pintype "passive"))
      (node (ref "S4") (pin "1") (pinfunction "1_1") (pintype "passive"))
      (node (ref "S4") (pin "2") (pinfunction "2_2") (pintype "passive"))
    )
    (net (code "41") (name "/D9") (class "Default")
      (node (ref "M1") (pin "4") (pinfunction "CSN_4") (pintype "bidirectional"))
      (node (ref "R19") (pin "2") (pinfunction "2_2") (pintype "passive"))
      (node (ref "S12") (pin "12") (pinfunction "12_12") (pintype "passive"))
      (node (ref "S5") (pin "1") (pinfunction "1_1") (pintype "passive"))
      (node (ref "S5") (pin "2") (pinfunction "2_2") (pintype "passive"))
    )
    (net (code "42") (name "/D10") (class "Default")
      (node (ref "R8") (pin "1") (pinfunction "1_1") (pintype "passive"))
      (node (ref "S12") (pin "13") (pinfunction "13_13") (pintype "passive"))
      (node (ref "S6") (pin "3") (pinfunction "3_3") (pintype "passive"))
    )
    (net (code "43") (name "/D11") (class "Default")
      (node (ref "R7") (pin "1") (pinfunction "1_1") (pintype "passive"))
      (node (ref "S12") (pin "14") (pinfunction "14_14") (pintype "passive"))
      (node (ref "S6") (pin "2") (pinfunction "2_2") (pintype "passive"))
    )
    (net (code "44") (name "/D12") (class "Default")
      (node (ref "R6") (pin "1") (pinfunction "1_1") (pintype "passive"))
      (node (ref "S12") (pin "15") (pinfunction "15_15") (pintype "passive"))
      (node (ref "S6") (pin "1") (pinfunction "1_1") (pintype "passive"))
    )
    (net (code "45") (name "/D13") (class "Default")
      (node (ref "IC3") (pin "5") (pinfunction "+IN_5") (pintype "input"))
      (node (ref "S12") (pin "16") (pinfunction "16_16") (pintype "passive"))
    )
    (net (code "46") (name "/DB4") (class "Default")
      (node (ref "IC4") (pin "13") (pinfunction "GP3_13") (pintype "bidirectional"))
      (node (ref "U1") (pin "11") (pinfunction "DB4_11") (pintype "bidirectional"))
    )
    (net (code "47") (name "/DB5") (class "Default")
      (node (ref "IC4") (pin "14") (pinfunction "GP4_14") (pintype "bidirectional"))
      (node (ref "U1") (pin "12") (pinfunction "DB5_12") (pintype "bidirectional"))
    )
    (net (code "48") (name "/DB6") (class "Default")
      (node (ref "IC4") (pin "15") (pinfunction "GP5_15") (pintype "bidirectional"))
      (node (ref "U1") (pin "13") (pinfunction "DB6_13") (pintype "bidirectional"))
    )
    (net (code "49") (name "/DB7") (class "Default")
      (node (ref "IC4") (pin "16") (pinfunction "GP6_16") (pintype "bidirectional"))
      (node (ref "U1") (pin "14") (pinfunction "DB7_14") (pintype "bidirectional"))
    )
    (net (code "50") (name "/DIO0") (class "Default")
      (node (ref "U$10") (pin "20") (pinfunction "DIO0_20") (pintype "bidirectional"))
    )
    (net (code "51") (name "/DIO1") (class "Default")
      (node (ref "U$10") (pin "19") (pinfunction "DIO1_19") (pintype "bidirectional"))
    )
    (net (code "52") (name "/DIO2") (class "Default")
      (node (ref "U$10") (pin "18") (pinfunction "DIO2_18") (pintype "bidirectional"))
    )
    (net (code "53") (name "/DIO3") (class "Default")
      (node (ref "U$10") (pin "17") (pinfunction "DIO3_17") (pintype "bidirectional"))
    )
    (net (code "54") (name "/DIO4") (class "Default")
      (node (ref "U$10") (pin "11") (pinfunction "DIO4_11") (pintype "bidirectional"))
    )
    (net (code "55") (name "/DIO5") (class "Default")
      (node (ref "U$10") (pin "15") (pinfunction "DIO5_15") (pintype "bidirectional"))
    )
    (net (code "56") (name "/DIO9") (class "Default")
      (node (ref "U$10") (pin "13") (pinfunction "DIO9_13") (pintype "bidirectional"))
    )
    (net (code "57") (name "/DIO11") (class "Default")
      (node (ref "U$10") (pin "7") (pinfunction "DIO11_7") (pintype "bidirectional"))
    )
    (net (code "58") (name "/DIO12") (class "Default")
      (node (ref "U$10") (pin "4") (pinfunction "DIO12_4") (pintype "bidirectional"))
    )
    (net (code "59") (name "/DTR") (class "Default")
      (node (ref "U$10") (pin "9") (pinfunction "DTR_9") (pintype "bidirectional"))
    )
    (net (code "60") (name "/E") (class "Default")
      (node (ref "IC4") (pin "12") (pinfunction "GP2_12") (pintype "bidirectional"))
      (node (ref "U1") (pin "6") (pinfunction "E_6") (pintype "input"))
    )
    (net (code "61") (name "/IOREF") (class "Default")
      (node (ref "U$4") (pin "IOREF") (pinfunction "IOREF_IOREF") (pintype "output"))
    )
    (net (code "62") (name "/LED") (class "Default")
      (node (ref "74HC4050") (pin "10") (pinfunction "4Y_10") (pintype "bidirectional"))
      (node (ref "R33") (pin "2") (pinfunction "2_2") (pintype "passive"))
    )
    (net (code "63") (name "/LIGHT") (class "Default")
      (node (ref "IC4") (pin "17") (pinfunction "GP7_17") (pintype "bidirectional"))
      (node (ref "R31") (pin "2") (pinfunction "2_2") (pintype "passive"))
    )
    (net (code "64") (name "/MISO") (class "Default")
      (node (ref "S14") (pin "4") (pinfunction "4_4") (pintype "passive"))
      (node (ref "U5") (pin "7") (pinfunction "DO_7") (pintype "bidirectional"))
    )
    (net (code "65") (name "/MOSI") (class "Default")
      (node (ref "74HC4050") (pin "5") (pinfunction "2A_5") (pintype "bidirectional"))
      (node (ref "S14") (pin "6") (pinfunction "6_6") (pintype "passive"))
    )
    (net (code "66") (name "/RES") (class "Default")
      (node (ref "U$10") (pin "8") (pinfunction "RES_8") (pintype "bidirectional"))
    )
    (net (code "67") (name "/RES1") (class "Default")
      (node (ref "U$10") (pin "14") (pinfunction "RES_14") (pintype "bidirectional"))
    )
    (net (code "68") (name "/RESET") (class "Default")
      (node (ref "U$10") (pin "5") (pinfunction "RESET_5") (pintype "input"))
    )
    (net (code "69") (name "/RS") (class "Default")
      (node (ref "IC4") (pin "11") (pinfunction "GP1_11") (pintype "bidirectional"))
      (node (ref "U1") (pin "4") (pinfunction "RS_4") (pintype "input"))
    )
    (net (code "70") (name "/RSSI") (class "Default")
      (node (ref "R41") (pin "2") (pinfunction "2_2") (pintype "passive"))
      (node (ref "U$10") (pin "6") (pinfunction "RSSI_6") (pintype "bidirectional"))
    )
    (net (code "71") (name "/RTS") (class "Default")
      (node (ref "U$10") (pin "16") (pinfunction "RTS_16") (pintype "input"))
    )
    (net (code "72") (name "/RX") (class "Default")
      (node (ref "BLUETOOTH") (pin "3") (pinfunction "3_3") (pintype "passive"))
      (node (ref "Q3") (pin "3") (pinfunction "D_3") (pintype "passive"))
      (node (ref "R38") (pin "1") (pinfunction "1_1") (pintype "passive"))
      (node (ref "S11") (pin "9") (pinfunction "9_9") (pintype "passive"))
    )
    (net (code "73") (name "/RXLED") (class "Default")
      (node (ref "LED2") (pin "C") (pinfunction "C_C") (pintype "passive"))
      (node (ref "U$1") (pin "8") (pinfunction "PB0(SS)_8") (pintype "bidirectional"))
    )
    (net (code "74") (name "/SCK") (class "Default")
      (node (ref "74HC4050") (pin "7") (pinfunction "3A_7") (pintype "bidirectional"))
      (node (ref "74HC4050") (pin "9") (pinfunction "4A_9") (pintype "bidirectional"))
      (node (ref "S14") (pin "5") (pinfunction "5_5") (pintype "passive"))
    )
    (net (code "75") (name "/SCL") (class "Default")
      (node (ref "IC4") (pin "1") (pinfunction "SCL_1") (pintype "bidirectional"))
      (node (ref "R35") (pin "1") (pinfunction "1_1") (pintype "passive"))
      (node (ref "S11") (pin "12") (pinfunction "12_12") (pintype "passive"))
      (node (ref "S12") (pin "20") (pinfunction "20_20") (pintype "passive"))
      (node (ref "U$7") (pin "6") (pinfunction "SCL_6") (pintype "bidirectional"))
      (node (ref "U2") (pin "6") (pinfunction "SCL_6") (pintype "bidirectional"))
    )
    (net (code "76") (name "/SDA") (class "Default")
      (node (ref "IC4") (pin "2") (pinfunction "SDA_2") (pintype "bidirectional"))
      (node (ref "R32") (pin "1") (pinfunction "1_1") (pintype "passive"))
      (node (ref "S11") (pin "11") (pinfunction "11_11") (pintype "passive"))
      (node (ref "S12") (pin "19") (pinfunction "19_19") (pintype "passive"))
      (node (ref "U$7") (pin "5") (pinfunction "SDA_5") (pintype "bidirectional"))
      (node (ref "U2") (pin "5") (pinfunction "SDA_5") (pintype "bidirectional"))
    )
    (net (code "77") (name "/SQW") (class "Default")
      (node (ref "U$7") (pin "7") (pinfunction "SQW_7") (pintype "bidirectional"))
    )
    (net (code "78") (name "/S_D10") (class "Default")
      (node (ref "IC6") (pin "1") (pinfunction "DIN_1") (pintype "input"))
      (node (ref "S6") (pin "4") (pinfunction "4_4") (pintype "passive"))
    )
    (net (code "79") (name "/S_D11") (class "Default")
      (node (ref "IC6") (pin "12") (pinfunction "LOAD_12") (pintype "input"))
      (node (ref "S6") (pin "5") (pinfunction "5_5") (pintype "passive"))
    )
    (net (code "80") (name "/S_D12") (class "Default")
      (node (ref "IC6") (pin "13") (pinfunction "CLK_13") (pintype "input"))
      (node (ref "S6") (pin "6") (pinfunction "6_6") (pintype "passive"))
    )
    (net (code "81") (name "/TX") (class "Default")
      (node (ref "BLUETOOTH") (pin "4") (pinfunction "4_4") (pintype "passive"))
      (node (ref "Q4") (pin "3") (pinfunction "D_3") (pintype "passive"))
      (node (ref "R40") (pin "1") (pinfunction "1_1") (pintype "passive"))
      (node (ref "S11") (pin "10") (pinfunction "10_10") (pintype "passive"))
    )
    (net (code "82") (name "/TXLED") (class "Default")
      (node (ref "LED8") (pin "C") (pinfunction "C_C") (pintype "passive"))
      (node (ref "U$1") (pin "22") (pinfunction "PD5_22") (pintype "bidirectional"))
    )
    (net (code "83") (name "/VUSB") (class "Default")
      (node (ref "C19") (pin "1") (pinfunction "1_1") (pintype "passive"))
      (node (ref "C20") (pin "A") (pinfunction "+_A") (pintype "passive"))
      (node (ref "FDN340") (pin "1") (pinfunction "D_1") (pintype "passive"))
      (node (ref "L1") (pin "2") (pinfunction "2_2") (pintype "passive"))
      (node (ref "U$1") (pin "7") (pinfunction "VBUS_7") (pintype "bidirectional"))
    )
    (net (code "84") (name "/~{RESET}") (class "Default")
      (node (ref "J1") (pin "5") (pinfunction "5_5") (pintype "passive"))
      (node (ref "JP5") (pin "5") (pinfunction "5_5") (pintype "passive"))
      (node (ref "R48") (pin "1") (pinfunction "1_1") (pintype "passive"))
      (node (ref "S1") (pin "1") (pinfunction "1_1") (pintype "passive"))
      (node (ref "S1") (pin "2") (pinfunction "2_2") (pintype "passive"))
      (node (ref "U$1") (pin "13") (pinfunction "~{RESET}_13") (pintype "bidirectional"))
      (node (ref "U$4") (pin "RESET") (pinfunction "/RESET_RESET") (pintype "bidirectional"))
    )
    (net (code "85") (name "3.3V") (class "Default")
      (node (ref "74HC4050") (pin "1") (pinfunction "VCC_1") (pintype "bidirectional"))
      (node (ref "C11") (pin "1") (pinfunction "1_1") (pintype "passive"))
      (node (ref "C12") (pin "A") (pinfunction "+_A") (pintype "passive"))
      (node (ref "C17") (pin "1") (pinfunction "1_1") (pintype "passive"))
      (node (ref "C27") (pin "1") (pinfunction "1_1") (pintype "passive"))
      (node (ref "IC3") (pin "2") (pinfunction "-IN_2") (pintype "input"))
      (node (ref "IC5") (pin "4") (pinfunction "OUT_4") (pintype "passive"))
      (node (ref "JP8") (pin "2") (pinfunction "2_2") (pintype "passive"))
      (node (ref "JP8") (pin "3") (pinfunction "3_3") (pintype "passive"))
      (node (ref "JP8") (pin "5") (pinfunction "5_5") (pintype "passive"))
      (node (ref "JP8") (pin "6") (pinfunction "6_6") (pintype "passive"))
      (node (ref "Q3") (pin "1") (pinfunction "G_1") (pintype "passive"))
      (node (ref "Q4") (pin "1") (pinfunction "G_1") (pintype "passive"))
      (node (ref "R37") (pin "2") (pinfunction "2_2") (pintype "passive"))
      (node (ref "R39") (pin "2") (pinfunction "2_2") (pintype "passive"))
      (node (ref "R42") (pin "2") (pinfunction "2_2") (pintype "passive"))
      (node (ref "R43") (pin "2") (pinfunction "2_2") (pintype "passive"))
      (node (ref "U$10") (pin "1") (pinfunction "VDD_1") (pintype "power_in"))
      (node (ref "U$4") (pin "3V") (pinfunction "3V_3V") (pintype "power_in"))
      (node (ref "U5") (pin "4") (pinfunction "VCC_4") (pintype "bidirectional"))
    )
    (net (code "86") (name "DIN") (class "Default")
      (node (ref "JP8") (pin "1") (pinfunction "1_1") (pintype "passive"))
      (node (ref "LED12") (pin "C") (pinfunction "C_C") (pintype "passive"))
      (node (ref "Q4") (pin "2") (pinfunction "S_2") (pintype "passive"))
      (node (ref "R39") (pin "1") (pinfunction "1_1") (pintype "passive"))
      (node (ref "U$10") (pin "3") (pinfunction "DIN_3") (pintype "input"))
    )
    (net (code "87") (name "DOUT") (class "Default")
      (node (ref "JP8") (pin "8") (pinfunction "8_8") (pintype "passive"))
      (node (ref "LED11") (pin "C") (pinfunction "C_C") (pintype "passive"))
      (node (ref "Q3") (pin "2") (pinfunction "S_2") (pintype "passive"))
      (node (ref "R37") (pin "1") (pinfunction "1_1") (pintype "passive"))
      (node (ref "U$10") (pin "2") (pinfunction "DOUT_2") (pintype "output"))
    )
    (net (code "88") (name "GND") (class "Default")
      (node (ref "74HC4050") (pin "11") (pinfunction "5A_11") (pintype "bidirectional"))
      (node (ref "74HC4050") (pin "14") (pinfunction "6A_14") (pintype "bidirectional"))
      (node (ref "74HC4050") (pin "8") (pinfunction "GND_8") (pintype "bidirectional"))
      (node (ref "BC847") (pin "E") (pinfunction "E_E") (pintype "passive"))
      (node (ref "BLUETOOTH") (pin "2") (pinfunction "2_2") (pintype "passive"))
      (node (ref "C1") (pin "1") (pinfunction "1_1") (pintype "passive"))
      (node (ref "C10") (pin "C") (pinfunction "-_C") (pintype "passive"))
      (node (ref "C11") (pin "2") (pinfunction "2_2") (pintype "passive"))
      (node (ref "C12") (pin "C") (pinfunction "-_C") (pintype "passive"))
      (node (ref "C13") (pin "2") (pinfunction "2_2") (pintype "passive"))
      (node (ref "C14") (pin "C") (pinfunction "-_C") (pintype "passive"))
      (node (ref "C15") (pin "2") (pinfunction "2_2") (pintype "passive"))
      (node (ref "C16") (pin "2") (pinfunction "2_2") (pintype "passive"))
      (node (ref "C17") (pin "2") (pinfunction "2_2") (pintype "passive"))
      (node (ref "C18") (pin "2") (pinfunction "2_2") (pintype "passive"))
      (node (ref "C19") (pin "2") (pinfunction "2_2") (pintype "passive"))
      (node (ref "C2") (pin "1") (pinfunction "1_1") (pintype "passive"))
      (node (ref "C20") (pin "C") (pinfunction "-_C") (pintype "passive"))
      (node (ref "C21") (pin "2") (pinfunction "2_2") (pintype "passive"))
      (node (ref "C22") (pin "2") (pinfunction "2_2") (pintype "passive"))
      (node (ref "C23") (pin "2") (pinfunction "2_2") (pintype "passive"))
      (node (ref "C24") (pin "2") (pinfunction "2_2") (pintype "passive"))
      (node (ref "C25") (pin "2") (pinfunction "2_2") (pintype "passive"))
      (node (ref "C26") (pin "2") (pinfunction "2_2") (pintype "passive"))
      (node (ref "C27") (pin "2") (pinfunction "2_2") (pintype "passive"))
      (node (ref "C28") (pin "-") (pinfunction "-_-") (pintype "passive"))
      (node (ref "C3") (pin "1") (pinfunction "1_1") (pintype "passive"))
      (node (ref "C30") (pin "-") (pinfunction "-_-") (pintype "passive"))
      (node (ref "C4") (pin "1") (pinfunction "1_1") (pintype "passive"))
      (node (ref "C5") (pin "1") (pinfunction "1_1") (pintype "passive"))
      (node (ref "C6") (pin "2") (pinfunction "2_2") (pintype "passive"))
      (node (ref "D1") (pin "A") (pinfunction "A_A") (pintype "passive"))
      (node (ref "IC1") (pin "3") (pinfunction "GND_3") (pintype "power_in"))
      (node (ref "IC1") (pin "5") (pinfunction "OFF_5") (pintype "input"))
      (node (ref "IC1") (pin "GND") (pinfunction "TAB_GND") (pintype "bidirectional"))
      (node (ref "IC2") (pin "3") (pinfunction "GND_3") (pintype "power_in"))
      (node (ref "IC3") (pin "4") (pinfunction "V-_4") (pintype "power_in"))
      (node (ref "IC4") (pin "9") (pinfunction "GND_9") (pintype "power_in"))
      (node (ref "IC5") (pin "1") (pinfunction "ADJ_1") (pintype "input"))
      (node (ref "IC6") (pin "4") (pinfunction "GND_4") (pintype "power_in"))
      (node (ref "IC6") (pin "9") (pinfunction "GND_9") (pintype "power_in"))
      (node (ref "J1") (pin "6") (pinfunction "6_6") (pintype "passive"))
      (node (ref "J2") (pin "GND") (pinfunction "GND_GND") (pintype "bidirectional"))
      (node (ref "J2") (pin "GNDBREAK") (pinfunction "GNDBREAK_GNDBREAK") (pintype "bidirectional"))
      (node (ref "JP5") (pin "6") (pinfunction "6_6") (pintype "passive"))
      (node (ref "JP8") (pin "7") (pinfunction "7_7") (pintype "passive"))
      (node (ref "LED10") (pin "C") (pinfunction "C_C") (pintype "passive"))
      (node (ref "LED3") (pin "K") (pinfunction "C_K") (pintype "passive"))
      (node (ref "LED4") (pin "K") (pinfunction "C_K") (pintype "passive"))
      (node (ref "LED5") (pin "K") (pinfunction "C_K") (pintype "passive"))
      (node (ref "LED6") (pin "K") (pinfunction "C_K") (pintype "passive"))
      (node (ref "LED7") (pin "C") (pinfunction "C_C") (pintype "passive"))
      (node (ref "M1") (pin "1") (pinfunction "GND_1") (pintype "power_in"))
      (node (ref "P1") (pin "A") (pinfunction "A_A") (pintype "passive"))
      (node (ref "Q1") (pin "1") (pinfunction "G_1") (pintype "passive"))
      (node (ref "R10") (pin "2") (pinfunction "2_2") (pintype "passive"))
      (node (ref "R20") (pin "1") (pinfunction "1_1") (pintype "passive"))
      (node (ref "R22") (pin "1") (pinfunction "1_1") (pintype "passive"))
      (node (ref "R23") (pin "2") (pinfunction "P$2_2") (pintype "bidirectional"))
      (node (ref "R26") (pin "1") (pinfunction "1_1") (pintype "passive"))
      (node (ref "R28") (pin "2") (pinfunction "2_2") (pintype "passive"))
      (node (ref "R29") (pin "2") (pinfunction "2_2") (pintype "passive"))
      (node (ref "R30") (pin "2") (pinfunction "2_2") (pintype "passive"))
      (node (ref "R34") (pin "2") (pinfunction "2_2") (pintype "passive"))
      (node (ref "R44") (pin "2") (pinfunction "2_2") (pintype "passive"))
      (node (ref "R47") (pin "1") (pinfunction "1_1") (pintype "passive"))
      (node (ref "R5") (pin "2") (pinfunction "2_2") (pintype "passive"))
      (node (ref "S1") (pin "3") (pinfunction "3_3") (pintype "passive"))
      (node (ref "S1") (pin "4") (pinfunction "4_4") (pintype "passive"))
      (node (ref "S12") (pin "17") (pinfunction "17_17") (pintype "passive"))
      (node (ref "S12") (pin "4") (pinfunction "4_4") (pintype "passive"))
      (node (ref "S4") (pin "3") (pinfunction "3_3") (pintype "passive"))
      (node (ref "S4") (pin "4") (pinfunction "4_4") (pintype "passive"))
      (node (ref "S5") (pin "3") (pinfunction "3_3") (pintype "passive"))
      (node (ref "S5") (pin "4") (pinfunction "4_4") (pintype "passive"))
      (node (ref "SW1") (pin "C") (pinfunction "C_C") (pintype "passive"))
      (node (ref "T2") (pin "E") (pinfunction "E_E") (pintype "passive"))
      (node (ref "T3") (pin "E") (pinfunction "E_E") (pintype "passive"))
      (node (ref "T4") (pin "E") (pinfunction "E_E") (pintype "passive"))
      (node (ref "U$1") (pin "15") (pinfunction "GND_15") (pintype "bidirectional"))
      (node (ref "U$1") (pin "23") (pinfunction "GND_23") (pintype "bidirectional"))
      (node (ref "U$1") (pin "35") (pinfunction "GND_35") (pintype "bidirectional"))
      (node (ref "U$1") (pin "43") (pinfunction "GND_43") (pintype "bidirectional"))
      (node (ref "U$1") (pin "5") (pinfunction "UGND_5") (pintype "bidirectional"))
      (node (ref "U$10") (pin "10") (pinfunction "GND_10") (pintype "power_in"))
      (node (ref "U$3") (pin "GND") (pinfunction "GND_GND") (pintype "bidirectional"))
      (node (ref "U$3") (pin "S1") (pinfunction "P$1_S1") (pintype "bidirectional"))
      (node (ref "U$3") (pin "S2") (pinfunction "P$2_S2") (pintype "bidirectional"))
      (node (ref "U$4") (pin "GND") (pinfunction "GND_GND") (pintype "power_in"))
      (node (ref "U$4") (pin "GND1") (pinfunction "GND1_GND1") (pintype "power_in"))
      (node (ref "U$4") (pin "GND2") (pinfunction "GND2_GND2") (pintype "power_in"))
      (node (ref "U$5") (pin "1") (pinfunction "A_1") (pintype "passive"))
      (node (ref "U$6") (pin "-") (pinfunction "-_-") (pintype "passive"))
      (node (ref "U$7") (pin "4") (pinfunction "GND_4") (pintype "bidirectional"))
      (node (ref "U$9") (pin "P$1") (pinfunction "3_P$1") (pintype "passive"))
      (node (ref "U1") (pin "1") (pinfunction "VSS_1") (pintype "power_in"))
      (node (ref "U1") (pin "5") (pinfunction "R/W_5") (pintype "input"))
      (node (ref "U2") (pin "1") (pinfunction "A0_1") (pintype "bidirectional"))
      (node (ref "U2") (pin "2") (pinfunction "A1_2") (pintype "bidirectional"))
      (node (ref "U2") (pin "3") (pinfunction "A2_3") (pintype "bidirectional"))
      (node (ref "U2") (pin "4") (pinfunction "VSS_4") (pintype "power_in"))
      (node (ref "U2") (pin "7") (pinfunction "WP_7") (pintype "bidirectional"))
      (node (ref "U5") (pin "6") (pinfunction "GND_6") (pintype "bidirectional"))
      (node (ref "U5") (pin "CD1") (pinfunction "SHIELD_CD1") (pintype "bidirectional"))
      (node (ref "U5") (pin "CD2") (pinfunction "SHIELD_CD2") (pintype "bidirectional"))
      (node (ref "U5") (pin "GND1") (pinfunction "SHIELD_GND1") (pintype "bidirectional"))
      (node (ref "U5") (pin "GND3") (pinfunction "SHIELD_GND3") (pintype "bidirectional"))
    )
    (net (code "89") (name "Net-(74HC4050-1Y)") (class "Default")
      (node (ref "74HC4050") (pin "2") (pinfunction "1Y_2") (pintype "bidirectional"))
      (node (ref "LED9") (pin "C") (pinfunction "C_C") (pintype "passive"))
      (node (ref "U5") (pin "2") (pinfunction "CS_2") (pintype "bidirectional"))
    )
    (net (code "90") (name "Net-(74HC4050-2Y)") (class "Default")
      (node (ref "74HC4050") (pin "4") (pinfunction "2Y_4") (pintype "bidirectional"))
      (node (ref "U5") (pin "3") (pinfunction "DI_3") (pintype "bidirectional"))
    )
    (net (code "91") (name "Net-(74HC4050-3Y)") (class "Default")
      (node (ref "74HC4050") (pin "6") (pinfunction "3Y_6") (pintype "bidirectional"))
      (node (ref "U5") (pin "5") (pinfunction "SCK_5") (pintype "bidirectional"))
    )
    (net (code "92") (name "Net-(BC847-PadB)") (class "Default")
      (node (ref "BC847") (pin "B") (pinfunction "B_B") (pintype "passive"))
      (node (ref "R20") (pin "2") (pinfunction "2_2") (pintype "passive"))
      (node (ref "R9") (pin "2") (pinfunction "2_2") (pintype "passive"))
    )
    (net (code "93") (name "Net-(BC847-PadC)") (class "Default")
      (node (ref "BC847") (pin "C") (pinfunction "C_C") (pintype "passive"))
      (node (ref "MOTOR") (pin "2") (pinfunction "2_2") (pintype "passive"))
    )
    (net (code "94") (name "Net-(D2-PadA)") (class "Default")
      (node (ref "D2") (pin "A") (pinfunction "A_A") (pintype "passive"))
      (node (ref "K4") (pin "2") (pinfunction "2_2") (pintype "passive"))
      (node (ref "LED1") (pin "C") (pinfunction "C_C") (pintype "passive"))
      (node (ref "T3") (pin "C") (pinfunction "C_C") (pintype "passive"))
    )
    (net (code "95") (name "Net-(FDN340-G)") (class "Default")
      (node (ref "FDN340") (pin "3") (pinfunction "G_3") (pintype "passive"))
      (node (ref "IC3") (pin "1") (pinfunction "OUT_1") (pintype "output"))
    )
    (net (code "96") (name "Net-(IC1-OUT)") (class "Default")
      (node (ref "D1") (pin "C") (pinfunction "C_C") (pintype "passive"))
      (node (ref "IC1") (pin "2") (pinfunction "OUT_2") (pintype "output"))
      (node (ref "L2") (pin "1") (pinfunction "1_1") (pintype "passive"))
    )
    (net (code "97") (name "Net-(IC3A-+IN)") (class "Default")
      (node (ref "C18") (pin "1") (pinfunction "1_1") (pintype "passive"))
      (node (ref "IC3") (pin "3") (pinfunction "+IN_3") (pintype "input"))
      (node (ref "R34") (pin "1") (pinfunction "1_1") (pintype "passive"))
      (node (ref "R36") (pin "2") (pinfunction "2_2") (pintype "passive"))
    )
    (net (code "98") (name "Net-(IC3B--IN)") (class "Default")
      (node (ref "IC3") (pin "6") (pinfunction "-IN_6") (pintype "input"))
      (node (ref "IC3") (pin "7") (pinfunction "OUT_7") (pintype "output"))
      (node (ref "R1") (pin "1") (pinfunction "1_1") (pintype "passive"))
    )
    (net (code "99") (name "Net-(IC4-A0)") (class "Default")
      (node (ref "IC4") (pin "5") (pinfunction "A0_5") (pintype "input"))
      (node (ref "R28") (pin "1") (pinfunction "1_1") (pintype "passive"))
    )
    (net (code "100") (name "Net-(IC4-A1)") (class "Default")
      (node (ref "IC4") (pin "4") (pinfunction "A1_4") (pintype "input"))
      (node (ref "R29") (pin "1") (pinfunction "1_1") (pintype "passive"))
    )
    (net (code "101") (name "Net-(IC4-A2)") (class "Default")
      (node (ref "IC4") (pin "3") (pinfunction "A2_3") (pintype "input"))
      (node (ref "R30") (pin "1") (pinfunction "1_1") (pintype "passive"))
    )
    (net (code "102") (name "Net-(IC4-{slash}RST)") (class "Default")
      (node (ref "IC4") (pin "6") (pinfunction "/RST_6") (pintype "input"))
      (node (ref "R45") (pin "1") (pinfunction "1_1") (pintype "passive"))
    )
    (net (code "103") (name "Net-(IC6-DIG0)") (class "Default")
      (node (ref "IC6") (pin "2") (pinfunction "DIG0_2") (pintype "output"))
      (node (ref "U$13") (pin "12") (pinfunction "DIG1_12") (pintype "input"))
    )
    (net (code "104") (name "Net-(IC6-DIG1)") (class "Default")
      (node (ref "IC6") (pin "11") (pinfunction "DIG1_11") (pintype "output"))
      (node (ref "U$13") (pin "9") (pinfunction "DIG2_9") (pintype "input"))
    )
    (net (code "105") (name "Net-(IC6-DIG2)") (class "Default")
      (node (ref "IC6") (pin "6") (pinfunction "DIG2_6") (pintype "output"))
      (node (ref "U$13") (pin "8") (pinfunction "DIG3_8") (pintype "input"))
    )
    (net (code "106") (name "Net-(IC6-DIG3)") (class "Default")
      (node (ref "IC6") (pin "7") (pinfunction "DIG3_7") (pintype "output"))
      (node (ref "U$13") (pin "6") (pinfunction "DIG4_6") (pintype "input"))
    )
    (net (code "107") (name "Net-(IC6-ISET)") (class "Default")
      (node (ref "IC6") (pin "18") (pinfunction "ISET_18") (pintype "input"))
      (node (ref "R46") (pin "1") (pinfunction "1_1") (pintype "passive"))
    )
    (net (code "108") (name "Net-(IC6-SEGA)") (class "Default")
      (node (ref "IC6") (pin "14") (pinfunction "SEGA_14") (pintype "output"))
      (node (ref "U$13") (pin "11") (pinfunction "A_11") (pintype "input"))
    )
    (net (code "109") (name "Net-(IC6-SEGB)") (class "Default")
      (node (ref "IC6") (pin "16") (pinfunction "SEGB_16") (pintype "output"))
      (node (ref "U$13") (pin "7") (pinfunction "B_7") (pintype "input"))
    )
    (net (code "110") (name "Net-(IC6-SEGC)") (class "Default")
      (node (ref "IC6") (pin "20") (pinfunction "SEGC_20") (pintype "output"))
      (node (ref "U$13") (pin "4") (pinfunction "C_4") (pintype "input"))
    )
    (net (code "111") (name "Net-(IC6-SEGD)") (class "Default")
      (node (ref "IC6") (pin "23") (pinfunction "SEGD_23") (pintype "output"))
      (node (ref "U$13") (pin "2") (pinfunction "D_2") (pintype "input"))
    )
    (net (code "112") (name "Net-(IC6-SEGDP)") (class "Default")
      (node (ref "IC6") (pin "22") (pinfunction "SEGDP_22") (pintype "output"))
      (node (ref "U$13") (pin "3") (pinfunction "DP_3") (pintype "input"))
    )
    (net (code "113") (name "Net-(IC6-SEGE)") (class "Default")
      (node (ref "IC6") (pin "21") (pinfunction "SEGE_21") (pintype "output"))
      (node (ref "U$13") (pin "1") (pinfunction "E_1") (pintype "input"))
    )
    (net (code "114") (name "Net-(IC6-SEGF)") (class "Default")
      (node (ref "IC6") (pin "15") (pinfunction "SEGF_15") (pintype "output"))
      (node (ref "U$13") (pin "10") (pinfunction "F_10") (pintype "input"))
    )
    (net (code "115") (name "Net-(IC6-SEGG)") (class "Default")
      (node (ref "IC6") (pin "17") (pinfunction "SEGG_17") (pintype "output"))
      (node (ref "U$13") (pin "5") (pinfunction "G_5") (pintype "input"))
    )
    (net (code "116") (name "Net-(JP1-Pad1)") (class "Default")
      (node (ref "JP1") (pin "1") (pinfunction "1_1") (pintype "passive"))
      (node (ref "K4") (pin "S") (pinfunction "S_S") (pintype "passive"))
    )
    (net (code "117") (name "Net-(JP1-Pad2)") (class "Default")
      (node (ref "JP1") (pin "2") (pinfunction "2_2") (pintype "passive"))
      (node (ref "K4") (pin "P") (pinfunction "P_P") (pintype "passive"))
    )
    (net (code "118") (name "Net-(JP1-Pad3)") (class "Default")
      (node (ref "JP1") (pin "3") (pinfunction "3_3") (pintype "passive"))
      (node (ref "K4") (pin "O") (pinfunction "O_O") (pintype "passive"))
    )
    (net (code "119") (name "Net-(L1-Pad1)") (class "Default")
      (node (ref "L1") (pin "1") (pinfunction "1_1") (pintype "passive"))
      (node (ref "U$3") (pin "VBUS") (pinfunction "VBUS_VBUS") (pintype "bidirectional"))
    )
    (net (code "120") (name "Net-(LED1-PadA)") (class "Default")
      (node (ref "LED1") (pin "A") (pinfunction "A_A") (pintype "passive"))
      (node (ref "R15") (pin "1") (pinfunction "1_1") (pintype "passive"))
    )
    (net (code "121") (name "Net-(LED2-PadA)") (class "Default")
      (node (ref "LED2") (pin "A") (pinfunction "A_A") (pintype "passive"))
      (node (ref "R14") (pin "1") (pinfunction "1_1") (pintype "passive"))
    )
    (net (code "122") (name "Net-(LED3-PadA)") (class "Default")
      (node (ref "LED3") (pin "A") (pinfunction "A_A") (pintype "passive"))
      (node (ref "R1") (pin "2") (pinfunction "2_2") (pintype "passive"))
    )
    (net (code "123") (name "Net-(LED4-PadA)") (class "Default")
      (node (ref "LED4") (pin "A") (pinfunction "A_A") (pintype "passive"))
      (node (ref "R6") (pin "2") (pinfunction "2_2") (pintype "passive"))
    )
    (net (code "124") (name "Net-(LED5-PadA)") (class "Default")
      (node (ref "LED5") (pin "A") (pinfunction "A_A") (pintype "passive"))
      (node (ref "R7") (pin "2") (pinfunction "2_2") (pintype "passive"))
    )
    (net (code "125") (name "Net-(LED6-PadA)") (class "Default")
      (node (ref "LED6") (pin "A") (pinfunction "A_A") (pintype "passive"))
      (node (ref "R8") (pin "2") (pinfunction "2_2") (pintype "passive"))
    )
    (net (code "126") (name "Net-(LED7-PadA)") (class "Default")
      (node (ref "LED7") (pin "A") (pinfunction "A_A") (pintype "passive"))
      (node (ref "R16") (pin "1") (pinfunction "1_1") (pintype "passive"))
    )
    (net (code "127") (name "Net-(LED8-PadA)") (class "Default")
      (node (ref "LED8") (pin "A") (pinfunction "A_A") (pintype "passive"))
      (node (ref "R17") (pin "1") (pinfunction "1_1") (pintype "passive"))
    )
    (net (code "128") (name "Net-(LED9-PadA)") (class "Default")
      (node (ref "LED9") (pin "A") (pinfunction "A_A") (pintype "passive"))
      (node (ref "R33") (pin "1") (pinfunction "1_1") (pintype "passive"))
    )
    (net (code "129") (name "Net-(LED10-PadA)") (class "Default")
      (node (ref "LED10") (pin "A") (pinfunction "A_A") (pintype "passive"))
      (node (ref "R41") (pin "1") (pinfunction "1_1") (pintype "passive"))
    )
    (net (code "130") (name "Net-(LED11-PadA)") (class "Default")
      (node (ref "LED11") (pin "A") (pinfunction "A_A") (pintype "passive"))
      (node (ref "R42") (pin "1") (pinfunction "1_1") (pintype "passive"))
    )
    (net (code "131") (name "Net-(LED12-PadA)") (class "Default")
      (node (ref "LED12") (pin "A") (pinfunction "A_A") (pintype "passive"))
      (node (ref "R43") (pin "1") (pinfunction "1_1") (pintype "passive"))
    )
    (net (code "132") (name "Net-(LED13-PadA)") (class "Default")
      (node (ref "LED13") (pin "A") (pinfunction "A_A") (pintype "passive"))
      (node (ref "R47") (pin "2") (pinfunction "2_2") (pintype "passive"))
    )
    (net (code "133") (name "Net-(Q1-D)") (class "Default")
      (node (ref "LED13") (pin "C") (pinfunction "C_C") (pintype "passive"))
      (node (ref "Q1") (pin "3") (pinfunction "D_3") (pintype "passive"))
      (node (ref "S9") (pin "3") (pinfunction "S_3") (pintype "passive"))
    )
    (net (code "134") (name "Net-(R2-Pad2)") (class "Default")
      (node (ref "R2") (pin "2") (pinfunction "2_2") (pintype "passive"))
      (node (ref "U$3") (pin "D-") (pinfunction "D-_D-") (pintype "bidirectional"))
    )
    (net (code "135") (name "Net-(R3-Pad2)") (class "Default")
      (node (ref "R3") (pin "2") (pinfunction "2_2") (pintype "passive"))
      (node (ref "U$3") (pin "D+") (pinfunction "D+_D+") (pintype "bidirectional"))
    )
    (net (code "136") (name "Net-(R11-Pad1)") (class "Default")
      (node (ref "R11") (pin "1") (pinfunction "1_1") (pintype "passive"))
      (node (ref "S2") (pin "3") (pinfunction "3_3") (pintype "passive"))
      (node (ref "S2") (pin "4") (pinfunction "4_4") (pintype "passive"))
    )
    (net (code "137") (name "Net-(R12-Pad1)") (class "Default")
      (node (ref "R12") (pin "1") (pinfunction "1_1") (pintype "passive"))
      (node (ref "S3") (pin "3") (pinfunction "3_3") (pintype "passive"))
      (node (ref "S3") (pin "4") (pinfunction "4_4") (pintype "passive"))
    )
    (net (code "138") (name "Net-(R21-Pad2)") (class "Default")
      (node (ref "R21") (pin "2") (pinfunction "2_2") (pintype "passive"))
      (node (ref "R22") (pin "2") (pinfunction "2_2") (pintype "passive"))
      (node (ref "T2") (pin "B") (pinfunction "B_B") (pintype "passive"))
    )
    (net (code "139") (name "Net-(R25-Pad2)") (class "Default")
      (node (ref "R25") (pin "2") (pinfunction "2_2") (pintype "passive"))
      (node (ref "R26") (pin "2") (pinfunction "2_2") (pintype "passive"))
      (node (ref "T3") (pin "B") (pinfunction "B_B") (pintype "passive"))
    )
    (net (code "140") (name "Net-(R31-Pad1)") (class "Default")
      (node (ref "R31") (pin "1") (pinfunction "1_1") (pintype "passive"))
      (node (ref "R44") (pin "1") (pinfunction "1_1") (pintype "passive"))
      (node (ref "T4") (pin "B") (pinfunction "B_B") (pintype "passive"))
    )
    (net (code "141") (name "Net-(S9-P)") (class "Default")
      (node (ref "J2") (pin "PWR") (pinfunction "PWR_PWR") (pintype "bidirectional"))
      (node (ref "S9") (pin "2") (pinfunction "P_2") (pintype "passive"))
    )
    (net (code "142") (name "Net-(SG2-Pad-)") (class "Default")
      (node (ref "SG2") (pin "-") (pinfunction "-_-") (pintype "passive"))
      (node (ref "T2") (pin "C") (pinfunction "C_C") (pintype "passive"))
    )
    (net (code "143") (name "Net-(SW1B-2)") (class "Default")
      (node (ref "R27") (pin "2") (pinfunction "2_2") (pintype "passive"))
      (node (ref "SW1") (pin "P2") (pinfunction "2_P2") (pintype "passive"))
    )
    (net (code "144") (name "Net-(U$1-PE2{slash}~{HWB})") (class "Default")
      (node (ref "R5") (pin "1") (pinfunction "1_1") (pintype "passive"))
      (node (ref "U$1") (pin "33") (pinfunction "PE2/~{HWB}_33") (pintype "bidirectional"))
    )
    (net (code "145") (name "Net-(U$1-UCAP)") (class "Default")
      (node (ref "C1") (pin "2") (pinfunction "2_2") (pintype "passive"))
      (node (ref "U$1") (pin "6") (pinfunction "UCAP_6") (pintype "bidirectional"))
    )
    (net (code "146") (name "Net-(U$1-XTAL1)") (class "Default")
      (node (ref "C2") (pin "2") (pinfunction "2_2") (pintype "passive"))
      (node (ref "R4") (pin "2") (pinfunction "2_2") (pintype "passive"))
      (node (ref "U$1") (pin "17") (pinfunction "XTAL1_17") (pintype "bidirectional"))
      (node (ref "Y1") (pin "3") (pinfunction "2_3") (pintype "passive"))
    )
    (net (code "147") (name "Net-(U$1-XTAL2)") (class "Default")
      (node (ref "C3") (pin "2") (pinfunction "2_2") (pintype "passive"))
      (node (ref "R4") (pin "1") (pinfunction "1_1") (pintype "passive"))
      (node (ref "U$1") (pin "16") (pinfunction "XTAL2_16") (pintype "bidirectional"))
      (node (ref "Y1") (pin "1") (pinfunction "1_1") (pintype "passive"))
    )
    (net (code "148") (name "Net-(U$5-S)") (class "Default")
      (node (ref "U$5") (pin "2") (pinfunction "S_2") (pintype "passive"))
      (node (ref "U1") (pin "3") (pinfunction "VO_3") (pintype "bidirectional"))
    )
    (net (code "149") (name "Net-(U$6-+)") (class "Default")
      (node (ref "U$6") (pin "+$1") (pinfunction "+_+$1") (pintype "passive"))
      (node (ref "U$7") (pin "3") (pinfunction "VBATT_3") (pintype "bidirectional"))
    )
    (net (code "150") (name "Net-(U$7-X1)") (class "Default")
      (node (ref "U$7") (pin "1") (pinfunction "X1_1") (pintype "bidirectional"))
      (node (ref "U$9") (pin "2") (pinfunction "2_2") (pintype "passive"))
    )
    (net (code "151") (name "Net-(U$7-X2)") (class "Default")
      (node (ref "U$7") (pin "2") (pinfunction "X2_2") (pintype "bidirectional"))
      (node (ref "U$9") (pin "1") (pinfunction "1_1") (pintype "passive"))
    )
    (net (code "152") (name "Net-(U1-K)") (class "Default")
      (node (ref "T4") (pin "C") (pinfunction "C_C") (pintype "passive"))
      (node (ref "U1") (pin "16") (pinfunction "K_16") (pintype "power_in"))
    )
    (net (code "153") (name "VCC") (class "Default")
      (node (ref "C28") (pin "+") (pinfunction "+_+") (pintype "passive"))
      (node (ref "IC1") (pin "1") (pinfunction "VIN_1") (pintype "power_in"))
      (node (ref "Q1") (pin "2") (pinfunction "S_2") (pintype "passive"))
      (node (ref "R36") (pin "1") (pinfunction "1_1") (pintype "passive"))
      (node (ref "U$4") (pin "VIN") (pinfunction "VIN_VIN") (pintype "power_in"))
    )
    (net (code "154") (name "unconnected-(74HC4050-5Y-Pad12)") (class "Default")
      (node (ref "74HC4050") (pin "12") (pinfunction "5Y_12") (pintype "bidirectional"))
    )
    (net (code "155") (name "unconnected-(74HC4050-6Y-Pad15)") (class "Default")
      (node (ref "74HC4050") (pin "15") (pinfunction "6Y_15") (pintype "bidirectional"))
    )
    (net (code "156") (name "unconnected-(H1-MOUNT-PadB3,2)") (class "Default")
      (node (ref "H1") (pin "B3,2") (pinfunction "MOUNT_B3,2") (pintype "passive"))
    )
    (net (code "157") (name "unconnected-(H2-MOUNT-PadB3,2)") (class "Default")
      (node (ref "H2") (pin "B3,2") (pinfunction "MOUNT_B3,2") (pintype "passive"))
    )
    (net (code "158") (name "unconnected-(H3-MOUNT-PadB3,2)") (class "Default")
      (node (ref "H3") (pin "B3,2") (pinfunction "MOUNT_B3,2") (pintype "passive"))
    )
    (net (code "159") (name "unconnected-(H4-MOUNT-PadB3,2)") (class "Default")
      (node (ref "H4") (pin "B3,2") (pinfunction "MOUNT_B3,2") (pintype "passive"))
    )
    (net (code "160") (name "unconnected-(H5-MOUNT-PadB3,2)") (class "Default")
      (node (ref "H5") (pin "B3,2") (pinfunction "MOUNT_B3,2") (pintype "passive"))
    )
    (net (code "161") (name "unconnected-(H6-MOUNT-PadB3,2)") (class "Default")
      (node (ref "H6") (pin "B3,2") (pinfunction "MOUNT_B3,2") (pintype "passive"))
    )
    (net (code "162") (name "unconnected-(IC4-GP0-Pad10)") (class "Default")
      (node (ref "IC4") (pin "10") (pinfunction "GP0_10") (pintype "bidirectional"))
    )
    (net (code "163") (name "unconnected-(IC4-INT-Pad8)") (class "Default")
      (node (ref "IC4") (pin "8") (pinfunction "INT_8") (pintype "output"))
    )
    (net (code "164") (name "unconnected-(IC6-DIG4-Pad3)") (class "Default")
      (node (ref "IC6") (pin "3") (pinfunction "DIG4_3") (pintype "output"))
    )
    (net (code "165") (name "unconnected-(IC6-DIG5-Pad10)") (class "Default")
      (node (ref "IC6") (pin "10") (pinfunction "DIG5_10") (pintype "output"))
    )
    (net (code "166") (name "unconnected-(IC6-DIG6-Pad5)") (class "Default")
      (node (ref "IC6") (pin "5") (pinfunction "DIG6_5") (pintype "output"))
    )
    (net (code "167") (name "unconnected-(IC6-DIG7-Pad8)") (class "Default")
      (node (ref "IC6") (pin "8") (pinfunction "DIG7_8") (pintype "output"))
    )
    (net (code "168") (name "unconnected-(IC6-DOUT-Pad24)") (class "Default")
      (node (ref "IC6") (pin "24") (pinfunction "DOUT_24") (pintype "output"))
    )
    (net (code "169") (name "unconnected-(JP8-Pad4)") (class "Default")
      (node (ref "JP8") (pin "4") (pinfunction "4_4") (pintype "passive"))
    )
    (net (code "170") (name "unconnected-(M1-IRQ-Pad8)") (class "Default")
      (node (ref "M1") (pin "8") (pinfunction "IRQ_8") (pintype "bidirectional"))
    )
    (net (code "171") (name "unconnected-(S9-O-Pad1)") (class "Default")
      (node (ref "S9") (pin "1") (pinfunction "O_1") (pintype "passive"))
    )
    (net (code "172") (name "unconnected-(U$4-PadRESERVED)") (class "Default")
      (node (ref "U$4") (pin "RESERVED") (pinfunction "RESERVED_RESERVED") (pintype "no_connect"))
    )
    (net (code "173") (name "unconnected-(U$6-+1-Pad+$2)") (class "Default")
      (node (ref "U$6") (pin "+$2") (pinfunction "+1_+$2") (pintype "passive"))
    )
    (net (code "174") (name "unconnected-(U1-DB0-Pad7)") (class "Default")
      (node (ref "U1") (pin "7") (pinfunction "DB0_7") (pintype "bidirectional"))
    )
    (net (code "175") (name "unconnected-(U1-DB1-Pad8)") (class "Default")
      (node (ref "U1") (pin "8") (pinfunction "DB1_8") (pintype "bidirectional"))
    )
    (net (code "176") (name "unconnected-(U1-DB2-Pad9)") (class "Default")
      (node (ref "U1") (pin "9") (pinfunction "DB2_9") (pintype "bidirectional"))
    )
    (net (code "177") (name "unconnected-(U1-DB3-Pad10)") (class "Default")
      (node (ref "U1") (pin "10") (pinfunction "DB3_10") (pintype "bidirectional"))
    )
    (net (code "178") (name "unconnected-(U5-NC-Pad1)") (class "Default")
      (node (ref "U5") (pin "1") (pinfunction "NC_1") (pintype "bidirectional"))
    )
    (net (code "179") (name "unconnected-(U5-RSV-Pad8)") (class "Default")
      (node (ref "U5") (pin "8") (pinfunction "RSV_8") (pintype "bidirectional"))
    )
  )
)
